# Arch_GPRS.net
KiCad netlist of a schematic drawn in EAGLE
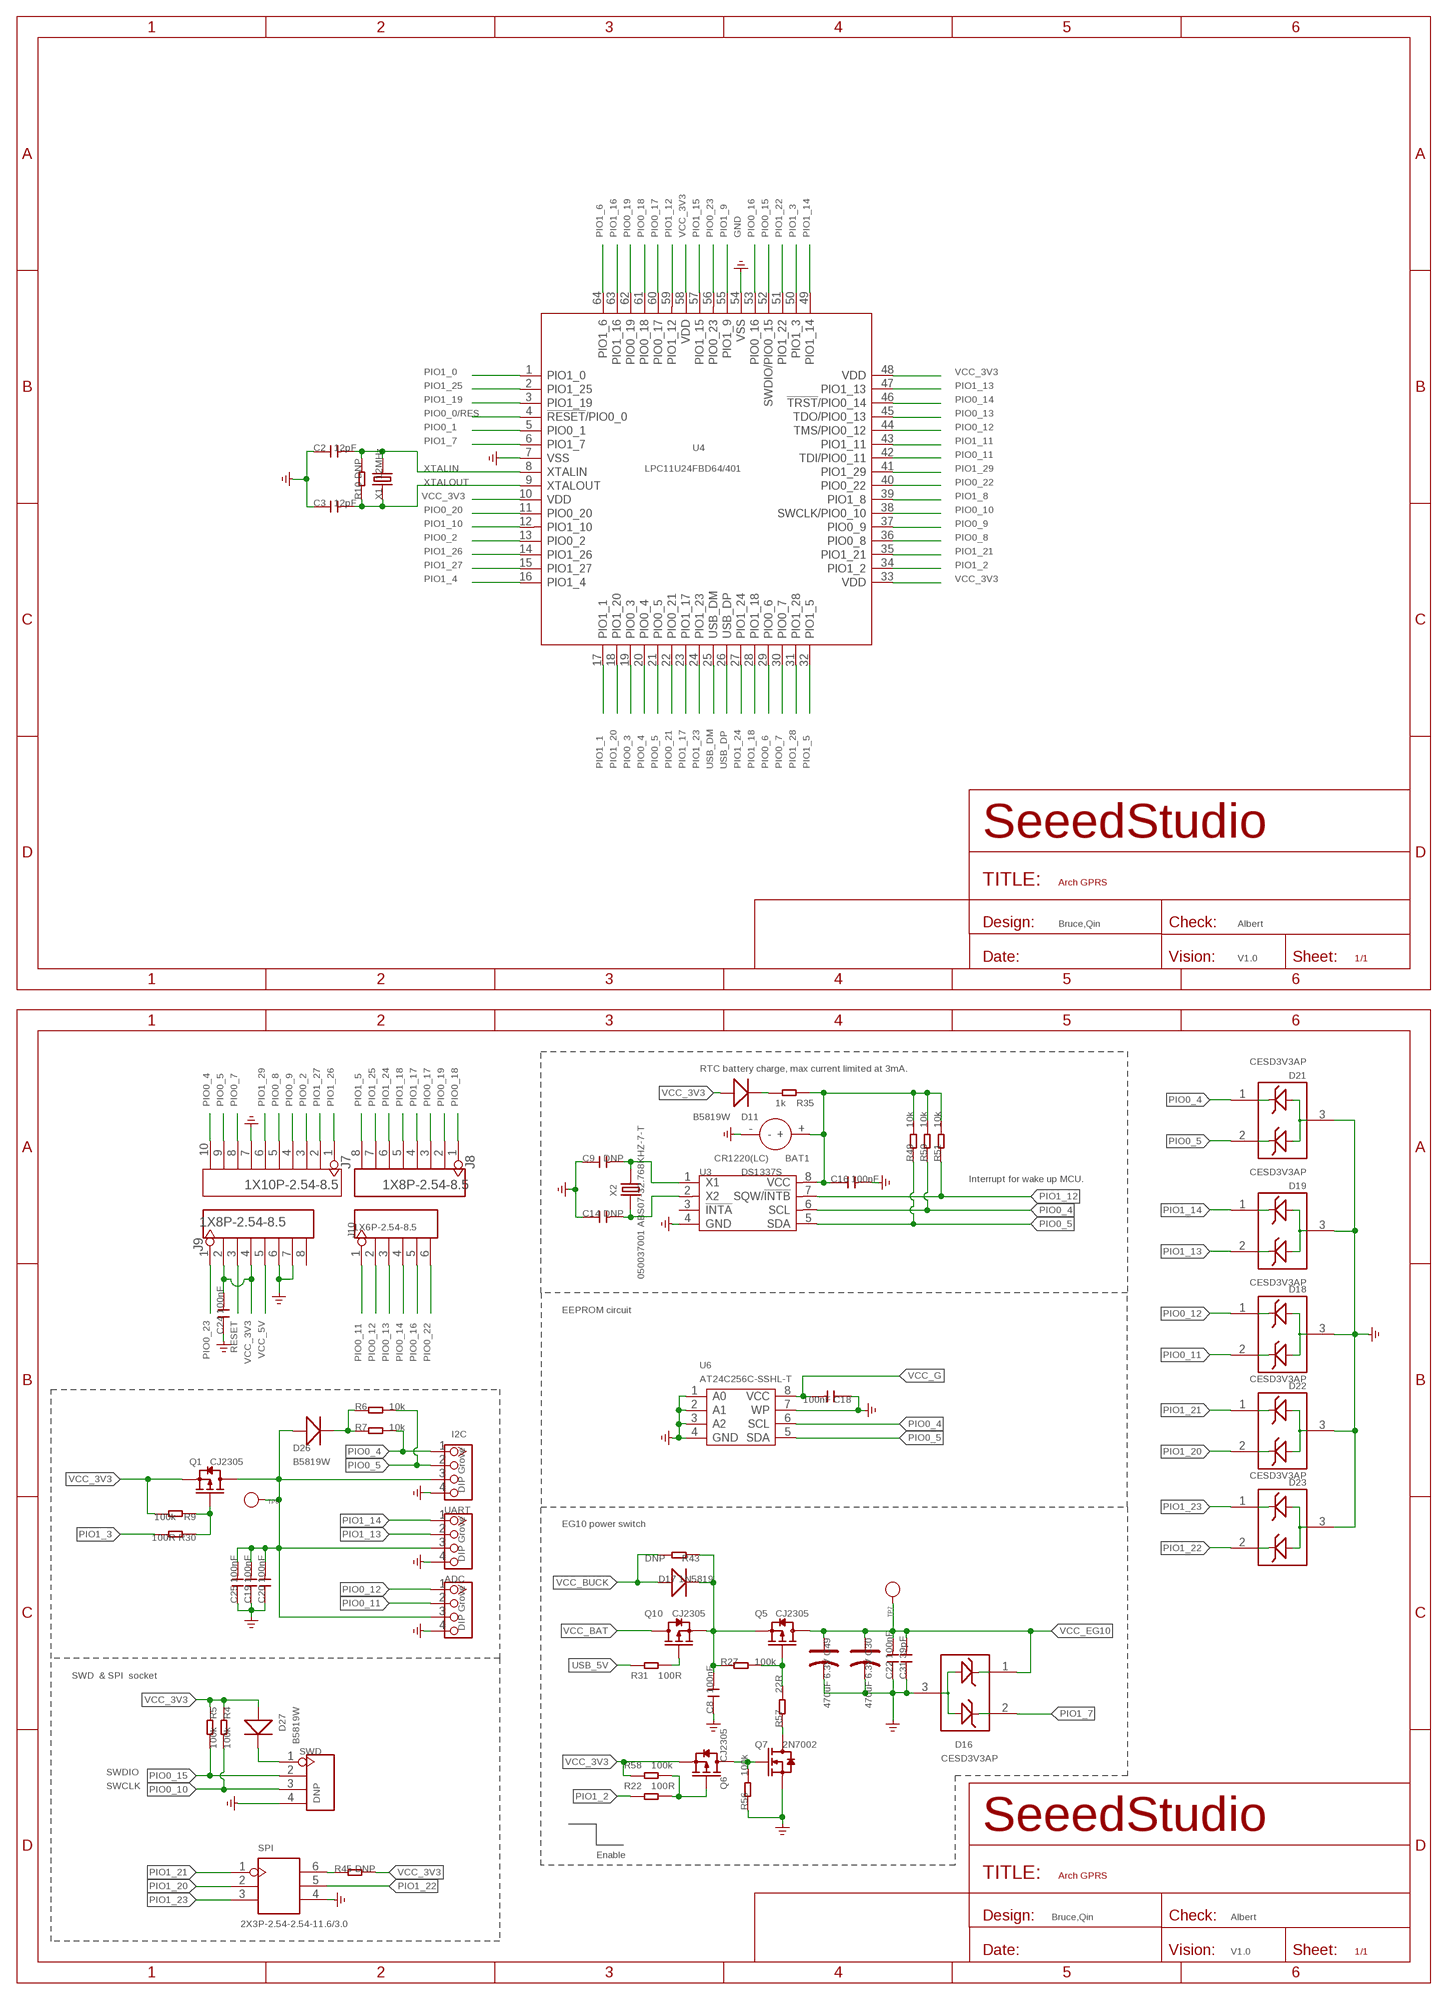
[diagram p0: schematic, sheet 1, part 1 of 2]
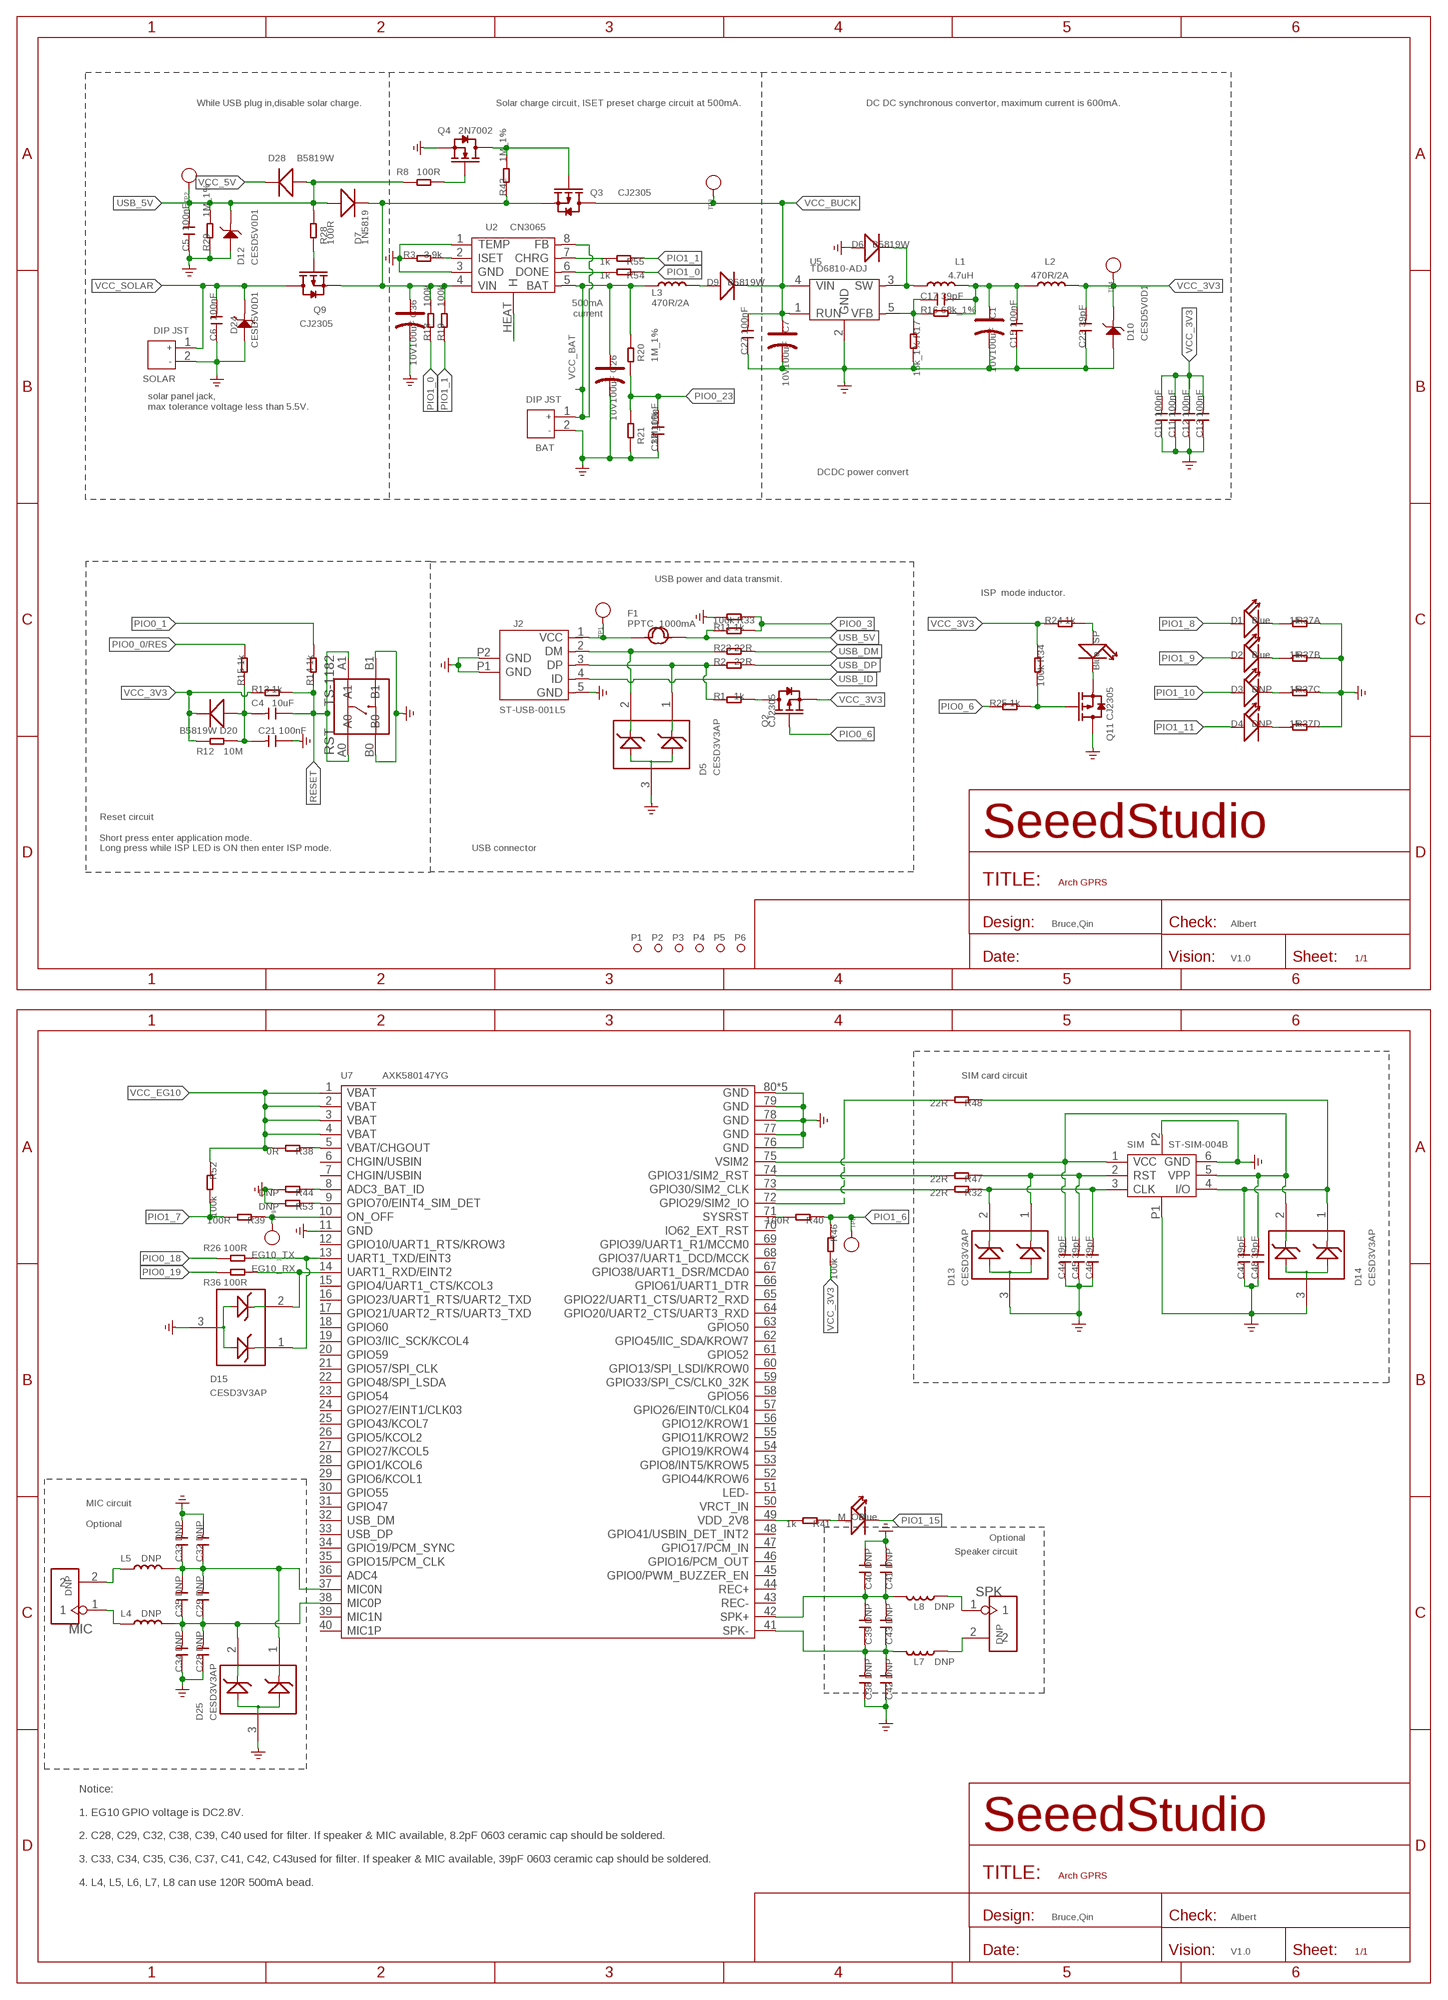
[diagram p1: schematic, sheet 1, part 2 of 2]

(export (version "E")
  (design (tool "Eeschema 10.0.6"))
  (components
    (comp (ref "ADC")
      (value "DIP Grove")
      (footprint "eagle-import:4P-2.0")
      (libsource (lib "eagle-import") (part "TWIG-4P-2.0-2.0"))
    )
    (comp (ref "BAT")
      (value "DIP JST")
      (footprint "eagle-import:JST-2.0")
      (libsource (lib "eagle-import") (part "JACK-JST-2P-PW'2.0'"))
    )
    (comp (ref "BAT1")
      (value "CR1220(LC)")
      (footprint "eagle-import:2P-D12.55X2.22H")
      (libsource (lib "eagle-import") (part "BATTERY-3V"))
    )
    (comp (ref "C1")
      (value "10V100uF")
      (footprint "eagle-import:AVX-B")
      (libsource (lib "eagle-import") (part "CAP-AVX-B"))
    )
    (comp (ref "C2")
      (value "12pF")
      (footprint "eagle-import:C0603")
      (libsource (lib "eagle-import") (part "C-0603"))
    )
    (comp (ref "C3")
      (value "12pF")
      (footprint "eagle-import:C0603")
      (libsource (lib "eagle-import") (part "C-0603"))
    )
    (comp (ref "C4")
      (value "10uF")
      (footprint "eagle-import:C0805")
      (libsource (lib "eagle-import") (part "C-0805"))
    )
    (comp (ref "C5")
      (value "100nF")
      (footprint "eagle-import:C0603")
      (libsource (lib "eagle-import") (part "C-0603"))
    )
    (comp (ref "C6")
      (value "100nF")
      (footprint "eagle-import:C0603")
      (libsource (lib "eagle-import") (part "C-0603"))
    )
    (comp (ref "C7")
      (value "10V100uF")
      (footprint "eagle-import:AVX-B")
      (libsource (lib "eagle-import") (part "CAP-AVX-B"))
    )
    (comp (ref "C8")
      (value "100nF")
      (footprint "eagle-import:C0603")
      (libsource (lib "eagle-import") (part "C-0603"))
    )
    (comp (ref "C9")
      (value "DNP")
      (footprint "eagle-import:C0603")
      (libsource (lib "eagle-import") (part "C-0603"))
    )
    (comp (ref "C10")
      (value "100nF")
      (footprint "eagle-import:C0603")
      (libsource (lib "eagle-import") (part "C-0603"))
    )
    (comp (ref "C11")
      (value "100nF")
      (footprint "eagle-import:C0603")
      (libsource (lib "eagle-import") (part "C-0603"))
    )
    (comp (ref "C12")
      (value "100nF")
      (footprint "eagle-import:C0603")
      (libsource (lib "eagle-import") (part "C-0603"))
    )
    (comp (ref "C13")
      (value "100nF")
      (footprint "eagle-import:C0603")
      (libsource (lib "eagle-import") (part "C-0603"))
    )
    (comp (ref "C14")
      (value "DNP")
      (footprint "eagle-import:C0603")
      (libsource (lib "eagle-import") (part "C-0603"))
    )
    (comp (ref "C15")
      (value "100nF")
      (footprint "eagle-import:C0603")
      (libsource (lib "eagle-import") (part "C-0603"))
    )
    (comp (ref "C16")
      (value "100nF")
      (footprint "eagle-import:C0603")
      (libsource (lib "eagle-import") (part "C-0603"))
    )
    (comp (ref "C17")
      (value "39pF")
      (footprint "eagle-import:C0603")
      (libsource (lib "eagle-import") (part "C-0603"))
    )
    (comp (ref "C18")
      (value "100nF")
      (footprint "eagle-import:C0603")
      (libsource (lib "eagle-import") (part "Discrete (1)_C-0603"))
    )
    (comp (ref "C19")
      (value "100nF")
      (footprint "eagle-import:C0603")
      (libsource (lib "eagle-import") (part "C-0603"))
    )
    (comp (ref "C20")
      (value "100nF")
      (footprint "eagle-import:C0603")
      (libsource (lib "eagle-import") (part "C-0603"))
    )
    (comp (ref "C21")
      (value "100nF")
      (footprint "eagle-import:C0603")
      (libsource (lib "eagle-import") (part "C-0603"))
    )
    (comp (ref "C22")
      (value "100nF")
      (footprint "eagle-import:C0603")
      (libsource (lib "eagle-import") (part "C-0603"))
    )
    (comp (ref "C23")
      (value "39pF")
      (footprint "eagle-import:C0603")
      (libsource (lib "eagle-import") (part "C-0603"))
    )
    (comp (ref "C24")
      (value "100nF")
      (footprint "eagle-import:C0603")
      (libsource (lib "eagle-import") (part "C-0603"))
    )
    (comp (ref "C25")
      (value "100nF")
      (footprint "eagle-import:C0603")
      (libsource (lib "eagle-import") (part "C-0603"))
    )
    (comp (ref "C26")
      (value "10V100uF")
      (footprint "eagle-import:AVX-B")
      (libsource (lib "eagle-import") (part "CAP-AVX-B"))
    )
    (comp (ref "C27")
      (value "100nF")
      (footprint "eagle-import:C0603")
      (libsource (lib "eagle-import") (part "C-0603"))
    )
    (comp (ref "C28")
      (value "DNP")
      (footprint "eagle-import:C0603")
      (libsource (lib "eagle-import") (part "C-0603"))
    )
    (comp (ref "C29")
      (value "DNP")
      (footprint "eagle-import:C0603")
      (libsource (lib "eagle-import") (part "C-0603"))
    )
    (comp (ref "C30")
      (value "470uF 6.3V")
      (footprint "eagle-import:AVX-D")
      (libsource (lib "eagle-import") (part "CAP-AVX-D"))
    )
    (comp (ref "C31")
      (value "39pF")
      (footprint "eagle-import:C0603")
      (libsource (lib "eagle-import") (part "C-0603"))
    )
    (comp (ref "C32")
      (value "DNP")
      (footprint "eagle-import:C0603")
      (libsource (lib "eagle-import") (part "C-0603"))
    )
    (comp (ref "C33")
      (value "DNP")
      (footprint "eagle-import:C0603")
      (libsource (lib "eagle-import") (part "C-0603"))
    )
    (comp (ref "C34")
      (value "DNP")
      (footprint "eagle-import:C0603")
      (libsource (lib "eagle-import") (part "C-0603"))
    )
    (comp (ref "C35")
      (value "DNP")
      (footprint "eagle-import:C0603")
      (libsource (lib "eagle-import") (part "C-0603"))
    )
    (comp (ref "C36")
      (value "10V100uF")
      (footprint "eagle-import:AVX-B")
      (libsource (lib "eagle-import") (part "CAP-AVX-B"))
    )
    (comp (ref "C37")
      (value "100nF")
      (footprint "eagle-import:C0603")
      (libsource (lib "eagle-import") (part "C-0603"))
    )
    (comp (ref "C38")
      (value "DNP")
      (footprint "eagle-import:C0603")
      (libsource (lib "eagle-import") (part "C-0603"))
    )
    (comp (ref "C39")
      (value "DNP")
      (footprint "eagle-import:C0603")
      (libsource (lib "eagle-import") (part "C-0603"))
    )
    (comp (ref "C40")
      (value "DNP")
      (footprint "eagle-import:C0603")
      (libsource (lib "eagle-import") (part "C-0603"))
    )
    (comp (ref "C41")
      (value "DNP")
      (footprint "eagle-import:C0603")
      (libsource (lib "eagle-import") (part "C-0603"))
    )
    (comp (ref "C42")
      (value "DNP")
      (footprint "eagle-import:C0603")
      (libsource (lib "eagle-import") (part "C-0603"))
    )
    (comp (ref "C43")
      (value "DNP")
      (footprint "eagle-import:C0603")
      (libsource (lib "eagle-import") (part "C-0603"))
    )
    (comp (ref "C44")
      (value "39pF")
      (footprint "eagle-import:C0603")
      (libsource (lib "eagle-import") (part "C-0603"))
    )
    (comp (ref "C45")
      (value "39pF")
      (footprint "eagle-import:C0603")
      (libsource (lib "eagle-import") (part "C-0603"))
    )
    (comp (ref "C46")
      (value "39pF")
      (footprint "eagle-import:C0603")
      (libsource (lib "eagle-import") (part "C-0603"))
    )
    (comp (ref "C47")
      (value "39pF")
      (footprint "eagle-import:C0603")
      (libsource (lib "eagle-import") (part "C-0603"))
    )
    (comp (ref "C48")
      (value "39pF")
      (footprint "eagle-import:C0603")
      (libsource (lib "eagle-import") (part "C-0603"))
    )
    (comp (ref "C49")
      (value "470uF 6.3V")
      (footprint "eagle-import:AVX-D")
      (libsource (lib "eagle-import") (part "CAP-AVX-D"))
    )
    (comp (ref "D1")
      (value "Blue")
      (footprint "eagle-import:LED-0603")
      (libsource (lib "eagle-import") (part "LED'0603'"))
    )
    (comp (ref "D2")
      (value "Blue")
      (footprint "eagle-import:LED-0603")
      (libsource (lib "eagle-import") (part "LED'0603'"))
    )
    (comp (ref "D3")
      (value "DNP")
      (footprint "eagle-import:LED-0603")
      (libsource (lib "eagle-import") (part "LED'0603'"))
    )
    (comp (ref "D4")
      (value "DNP")
      (footprint "eagle-import:LED-0603")
      (libsource (lib "eagle-import") (part "LED'0603'"))
    )
    (comp (ref "D5")
      (value "CESD3V3AP")
      (footprint "eagle-import:SOT23")
      (libsource (lib "eagle-import") (part "D-ESD-3P"))
    )
    (comp (ref "D6")
      (value "B5819W")
      (footprint "eagle-import:SOD123")
      (libsource (lib "eagle-import") (part "D'1206'"))
    )
    (comp (ref "D7")
      (value "1N5819")
      (footprint "eagle-import:SMA")
      (libsource (lib "eagle-import") (part "D'B130L-13-F'"))
    )
    (comp (ref "D9")
      (value "B5819W")
      (footprint "eagle-import:SOD123")
      (libsource (lib "eagle-import") (part "D'1206'"))
    )
    (comp (ref "D10")
      (value "CESD5V0D1")
      (footprint "eagle-import:SOD123-2.7X1.6")
      (libsource (lib "eagle-import") (part "D-ESD-2P'CESD5V0D1'"))
    )
    (comp (ref "D11")
      (value "B5819W")
      (footprint "eagle-import:SOD123")
      (libsource (lib "eagle-import") (part "D'1206'"))
    )
    (comp (ref "D12")
      (value "CESD5V0D1")
      (footprint "eagle-import:SOD123-2.7X1.6")
      (libsource (lib "eagle-import") (part "D-ESD-2P'CESD5V0D1'"))
    )
    (comp (ref "D13")
      (value "CESD3V3AP")
      (footprint "eagle-import:SOT23")
      (libsource (lib "eagle-import") (part "D-ESD-3P"))
    )
    (comp (ref "D14")
      (value "CESD3V3AP")
      (footprint "eagle-import:SOT23")
      (libsource (lib "eagle-import") (part "D-ESD-3P"))
    )
    (comp (ref "D15")
      (value "CESD3V3AP")
      (footprint "eagle-import:SOT23")
      (libsource (lib "eagle-import") (part "D-ESD-3P"))
    )
    (comp (ref "D16")
      (value "CESD3V3AP")
      (footprint "eagle-import:SOT23")
      (libsource (lib "eagle-import") (part "D-ESD-3P"))
    )
    (comp (ref "D17")
      (value "1N5819")
      (footprint "eagle-import:SMA")
      (libsource (lib "eagle-import") (part "D'B130L-13-F'"))
    )
    (comp (ref "D18")
      (value "CESD3V3AP")
      (footprint "eagle-import:SOT23")
      (libsource (lib "eagle-import") (part "D-ESD-3P"))
    )
    (comp (ref "D19")
      (value "CESD3V3AP")
      (footprint "eagle-import:SOT23")
      (libsource (lib "eagle-import") (part "D-ESD-3P"))
    )
    (comp (ref "D20")
      (value "B5819W")
      (footprint "eagle-import:SOD123")
      (libsource (lib "eagle-import") (part "D'1206'"))
    )
    (comp (ref "D21")
      (value "CESD3V3AP")
      (footprint "eagle-import:SOT23")
      (libsource (lib "eagle-import") (part "D-ESD-3P"))
    )
    (comp (ref "D22")
      (value "CESD3V3AP")
      (footprint "eagle-import:SOT23")
      (libsource (lib "eagle-import") (part "D-ESD-3P"))
    )
    (comp (ref "D23")
      (value "CESD3V3AP")
      (footprint "eagle-import:SOT23")
      (libsource (lib "eagle-import") (part "D-ESD-3P"))
    )
    (comp (ref "D24")
      (value "CESD5V0D1")
      (footprint "eagle-import:SOD123-2.7X1.6")
      (libsource (lib "eagle-import") (part "D-ESD-2P'CESD5V0D1'"))
    )
    (comp (ref "D25")
      (value "CESD3V3AP")
      (footprint "eagle-import:SOT23")
      (libsource (lib "eagle-import") (part "D-ESD-3P"))
    )
    (comp (ref "D26")
      (value "B5819W")
      (footprint "eagle-import:SOD123")
      (libsource (lib "eagle-import") (part "D'1206'"))
    )
    (comp (ref "D27")
      (value "B5819W")
      (footprint "eagle-import:SOD123")
      (libsource (lib "eagle-import") (part "D'1206'"))
    )
    (comp (ref "D28")
      (value "B5819W")
      (footprint "eagle-import:SOD123")
      (libsource (lib "eagle-import") (part "D'1206'"))
    )
    (comp (ref "F1")
      (value "PPTC_1000mA")
      (footprint "eagle-import:F1206")
      (libsource (lib "eagle-import") (part "FUSE'1206'"))
    )
    (comp (ref "I2C")
      (value "DIP Grove")
      (footprint "eagle-import:4P-2.0")
      (libsource (lib "eagle-import") (part "TWIG-4P-2.0-2.0"))
    )
    (comp (ref "ISP")
      (value "Blue")
      (footprint "eagle-import:LED-0603")
      (libsource (lib "eagle-import") (part "LED'0603'"))
    )
    (comp (ref "J2")
      (value "ST-USB-001L5")
      (footprint "eagle-import:MICRO-5P-180D")
      (libsource (lib "eagle-import") (part "USB-MICRO-5P'ST-USB-001L5'"))
    )
    (comp (ref "J7")
      (value "1X10P-2.54-8.5")
      (footprint "eagle-import:10P-2.54")
      (libsource (lib "eagle-import") (part "HEADER-10P-2.54"))
    )
    (comp (ref "J8")
      (value "1X8P-2.54-8.5")
      (footprint "eagle-import:8P-2.54")
      (libsource (lib "eagle-import") (part "HEADER-8P-2.54"))
    )
    (comp (ref "J9")
      (value "1X8P-2.54-8.5")
      (footprint "eagle-import:8P-2.54")
      (libsource (lib "eagle-import") (part "HEADER-8P-2.54"))
    )
    (comp (ref "J10")
      (value "1X6P-2.54-8.5")
      (footprint "eagle-import:6P-2.54-65_35MIL")
      (libsource (lib "eagle-import") (part "HEADER-6P-65/35MIL"))
    )
    (comp (ref "L1")
      (value "4.7uH")
      (footprint "eagle-import:L0420")
      (libsource (lib "eagle-import") (part "LSPD3D16-4R7M"))
    )
    (comp (ref "L2")
      (value "470R/2A")
      (footprint "eagle-import:L0805")
      (libsource (lib "eagle-import") (part "L'0805'"))
    )
    (comp (ref "L3")
      (value "470R/2A")
      (footprint "eagle-import:L0805")
      (libsource (lib "eagle-import") (part "L'0805'"))
    )
    (comp (ref "L4")
      (value "DNP")
      (footprint "eagle-import:L0603")
      (libsource (lib "eagle-import") (part "L'0603'"))
    )
    (comp (ref "L5")
      (value "DNP")
      (footprint "eagle-import:L0603")
      (libsource (lib "eagle-import") (part "L'0603'"))
    )
    (comp (ref "L7")
      (value "DNP")
      (footprint "eagle-import:L0603")
      (libsource (lib "eagle-import") (part "L'0603'"))
    )
    (comp (ref "L8")
      (value "DNP")
      (footprint "eagle-import:L0603")
      (libsource (lib "eagle-import") (part "L'0603'"))
    )
    (comp (ref "MIC")
      (value "DNP")
      (footprint "eagle-import:2P-2.0")
      (libsource (lib "eagle-import") (part "HEADER-2P-2.0"))
    )
    (comp (ref "M_ON")
      (value "Blue")
      (footprint "eagle-import:LED-0603")
      (libsource (lib "eagle-import") (part "LED'0603'"))
    )
    (comp (ref "P1")
      (value "PAD-MARK")
      (footprint "eagle-import:ROUND-MARK-1.0")
      (fields (field (name "PARTNO") "DNP"))
      (libsource (lib "eagle-import") (part "PAD-MARK"))
    )
    (comp (ref "P2")
      (value "PAD-MARK")
      (footprint "eagle-import:ROUND-MARK-1.0")
      (fields (field (name "PARTNO") "DNP"))
      (libsource (lib "eagle-import") (part "PAD-MARK"))
    )
    (comp (ref "P3")
      (value "PAD-MARK")
      (footprint "eagle-import:ROUND-MARK-1.0")
      (fields (field (name "PARTNO") "DNP"))
      (libsource (lib "eagle-import") (part "PAD-MARK"))
    )
    (comp (ref "P4")
      (value "PAD-MARK")
      (footprint "eagle-import:ROUND-MARK-1.0")
      (fields (field (name "PARTNO") "DNP"))
      (libsource (lib "eagle-import") (part "PAD-MARK"))
    )
    (comp (ref "P5")
      (value "PAD-MARK")
      (footprint "eagle-import:ROUND-MARK-1.0")
      (fields (field (name "PARTNO") "DNP"))
      (libsource (lib "eagle-import") (part "PAD-MARK"))
    )
    (comp (ref "P6")
      (value "PAD-MARK")
      (footprint "eagle-import:ROUND-MARK-1.0")
      (fields (field (name "PARTNO") "DNP"))
      (libsource (lib "eagle-import") (part "PAD-MARK"))
    )
    (comp (ref "Q1")
      (value "CJ2305")
      (footprint "eagle-import:SOT23")
      (libsource (lib "eagle-import") (part "MOSFET-P'SI2323CDS/SI2305DS{lt}BR{gt}'"))
    )
    (comp (ref "Q2")
      (value "CJ2305")
      (footprint "eagle-import:SOT23")
      (libsource (lib "eagle-import") (part "MOSFET-P'SI2323CDS/SI2305DS{lt}BR{gt}'"))
    )
    (comp (ref "Q3")
      (value "CJ2305")
      (footprint "eagle-import:SOT23")
      (libsource (lib "eagle-import") (part "MOSFET-P'SI2323CDS/SI2305DS{lt}BR{gt}'"))
    )
    (comp (ref "Q4")
      (value "2N7002")
      (footprint "eagle-import:SOT23")
      (libsource (lib "eagle-import") (part "MOSFET-N'SOT23'"))
    )
    (comp (ref "Q5")
      (value "CJ2305")
      (footprint "eagle-import:SOT23")
      (libsource (lib "eagle-import") (part "MOSFET-P'SI2323CDS/SI2305DS{lt}BR{gt}'"))
    )
    (comp (ref "Q6")
      (value "CJ2305")
      (footprint "eagle-import:SOT23")
      (libsource (lib "eagle-import") (part "MOSFET-P'SI2323CDS/SI2305DS{lt}BR{gt}'"))
    )
    (comp (ref "Q7")
      (value "2N7002")
      (footprint "eagle-import:SOT23")
      (libsource (lib "eagle-import") (part "MOSFET-N'SOT23'"))
    )
    (comp (ref "Q9")
      (value "CJ2305")
      (footprint "eagle-import:SOT23")
      (libsource (lib "eagle-import") (part "MOSFET-P'SI2323CDS/SI2305DS{lt}BR{gt}'"))
    )
    (comp (ref "Q10")
      (value "CJ2305")
      (footprint "eagle-import:SOT23")
      (libsource (lib "eagle-import") (part "MOSFET-P'SI2323CDS/SI2305DS{lt}BR{gt}'"))
    )
    (comp (ref "Q11")
      (value "CJ2305")
      (footprint "eagle-import:SOT23")
      (libsource (lib "eagle-import") (part "MOSFET-P'SI2323CDS/SI2305DS{lt}BR{gt}'"))
    )
    (comp (ref "R1")
      (value "1k")
      (footprint "eagle-import:R0603")
      (libsource (lib "eagle-import") (part "R-0603"))
    )
    (comp (ref "R2")
      (value "22R")
      (footprint "eagle-import:R0603")
      (libsource (lib "eagle-import") (part "R-0603"))
    )
    (comp (ref "R3")
      (value "3.9k")
      (footprint "eagle-import:R0603")
      (libsource (lib "eagle-import") (part "R-0603"))
    )
    (comp (ref "R4")
      (value "100k")
      (footprint "eagle-import:R0603")
      (libsource (lib "eagle-import") (part "R-0603"))
    )
    (comp (ref "R5")
      (value "100k")
      (footprint "eagle-import:R0603")
      (libsource (lib "eagle-import") (part "R-0603"))
    )
    (comp (ref "R6")
      (value "10k")
      (footprint "eagle-import:R0603")
      (libsource (lib "eagle-import") (part "R-0603"))
    )
    (comp (ref "R7")
      (value "10k")
      (footprint "eagle-import:R0603")
      (libsource (lib "eagle-import") (part "R-0603"))
    )
    (comp (ref "R8")
      (value "100R")
      (footprint "eagle-import:R0603")
      (libsource (lib "eagle-import") (part "R-0603"))
    )
    (comp (ref "R9")
      (value "100k")
      (footprint "eagle-import:R0603")
      (libsource (lib "eagle-import") (part "R-0603"))
    )
    (comp (ref "R10")
      (value "DNP")
      (footprint "eagle-import:R0603")
      (libsource (lib "eagle-import") (part "R-0603"))
    )
    (comp (ref "R11")
      (value "1k")
      (footprint "eagle-import:R0603")
      (libsource (lib "eagle-import") (part "R-0603"))
    )
    (comp (ref "R12")
      (value "10M")
      (footprint "eagle-import:R0603")
      (libsource (lib "eagle-import") (part "R-0603"))
    )
    (comp (ref "R13")
      (value "1k")
      (footprint "eagle-import:R0603")
      (libsource (lib "eagle-import") (part "R-0603"))
    )
    (comp (ref "R14")
      (value "1k")
      (footprint "eagle-import:R0603")
      (libsource (lib "eagle-import") (part "R-0603"))
    )
    (comp (ref "R15")
      (value "1k")
      (footprint "eagle-import:R0603")
      (libsource (lib "eagle-import") (part "R-0603"))
    )
    (comp (ref "R16")
      (value "68k_1%")
      (footprint "eagle-import:R0603")
      (libsource (lib "eagle-import") (part "R-0603"))
    )
    (comp (ref "R17")
      (value "15k_1%")
      (footprint "eagle-import:R0603")
      (libsource (lib "eagle-import") (part "R-0603"))
    )
    (comp (ref "R18")
      (value "100k")
      (footprint "eagle-import:R0603")
      (libsource (lib "eagle-import") (part "R-0603"))
    )
    (comp (ref "R19")
      (value "100k")
      (footprint "eagle-import:R0603")
      (libsource (lib "eagle-import") (part "R-0603"))
    )
    (comp (ref "R20")
      (value "1M_1%")
      (footprint "eagle-import:R0603")
      (libsource (lib "eagle-import") (part "R-0603"))
    )
    (comp (ref "R21")
      (value "1M_1%")
      (footprint "eagle-import:R0603")
      (libsource (lib "eagle-import") (part "R-0603"))
    )
    (comp (ref "R22")
      (value "100R")
      (footprint "eagle-import:R0603")
      (libsource (lib "eagle-import") (part "R-0603"))
    )
    (comp (ref "R23")
      (value "22R")
      (footprint "eagle-import:R0603")
      (libsource (lib "eagle-import") (part "R-0603"))
    )
    (comp (ref "R24")
      (value "1k")
      (footprint "eagle-import:R0603")
      (libsource (lib "eagle-import") (part "R-0603"))
    )
    (comp (ref "R25")
      (value "1k")
      (footprint "eagle-import:R0603")
      (libsource (lib "eagle-import") (part "R-0603"))
    )
    (comp (ref "R26")
      (value "100R")
      (footprint "eagle-import:R0603")
      (libsource (lib "eagle-import") (part "R-0603"))
    )
    (comp (ref "R27")
      (value "100k")
      (footprint "eagle-import:R0603")
      (libsource (lib "eagle-import") (part "R-0603"))
    )
    (comp (ref "R28")
      (value "100R")
      (footprint "eagle-import:R0603")
      (libsource (lib "eagle-import") (part "R-0603"))
    )
    (comp (ref "R29")
      (value "1M_1%")
      (footprint "eagle-import:R0603")
      (libsource (lib "eagle-import") (part "R-0603"))
    )
    (comp (ref "R30")
      (value "100R")
      (footprint "eagle-import:R0603")
      (libsource (lib "eagle-import") (part "R-0603"))
    )
    (comp (ref "R31")
      (value "100R")
      (footprint "eagle-import:R0603")
      (libsource (lib "eagle-import") (part "R-0603"))
    )
    (comp (ref "R32")
      (value "22R")
      (footprint "eagle-import:R0603")
      (libsource (lib "eagle-import") (part "R-0603"))
    )
    (comp (ref "R33")
      (value "100k")
      (footprint "eagle-import:R0603")
      (libsource (lib "eagle-import") (part "R-0603"))
    )
    (comp (ref "R34")
      (value "100k")
      (footprint "eagle-import:R0603")
      (libsource (lib "eagle-import") (part "R-0603"))
    )
    (comp (ref "R35")
      (value "1k")
      (footprint "eagle-import:R0603")
      (libsource (lib "eagle-import") (part "R-0603"))
    )
    (comp (ref "R36")
      (value "100R")
      (footprint "eagle-import:R0603")
      (libsource (lib "eagle-import") (part "R-0603"))
    )
    (comp (ref "R37")
      (value "1k")
      (footprint "eagle-import:1206-8-3.3X2.4")
      (libsource (lib "eagle-import") (part "R-4R-1206"))
    )
    (comp (ref "R38")
      (value "0R")
      (footprint "eagle-import:R0603")
      (libsource (lib "eagle-import") (part "R-0603"))
    )
    (comp (ref "R39")
      (value "100R")
      (footprint "eagle-import:R0603")
      (libsource (lib "eagle-import") (part "R-0603"))
    )
    (comp (ref "R40")
      (value "100R")
      (footprint "eagle-import:R0603")
      (libsource (lib "eagle-import") (part "R-0603"))
    )
    (comp (ref "R41")
      (value "1k")
      (footprint "eagle-import:R0603")
      (libsource (lib "eagle-import") (part "R-0603"))
    )
    (comp (ref "R42")
      (value "1M_1%")
      (footprint "eagle-import:R0603")
      (libsource (lib "eagle-import") (part "R-0603"))
    )
    (comp (ref "R43")
      (value "DNP")
      (footprint "eagle-import:R0603")
      (libsource (lib "eagle-import") (part "R-0603"))
    )
    (comp (ref "R44")
      (value "DNP")
      (footprint "eagle-import:R0603")
      (libsource (lib "eagle-import") (part "R-0603"))
    )
    (comp (ref "R45")
      (value "DNP")
      (footprint "eagle-import:R0603")
      (libsource (lib "eagle-import") (part "R-0603"))
    )
    (comp (ref "R46")
      (value "100k")
      (footprint "eagle-import:R0603")
      (libsource (lib "eagle-import") (part "R-0603"))
    )
    (comp (ref "R47")
      (value "22R")
      (footprint "eagle-import:R0603")
      (libsource (lib "eagle-import") (part "R-0603"))
    )
    (comp (ref "R48")
      (value "22R")
      (footprint "eagle-import:R0603")
      (libsource (lib "eagle-import") (part "R-0603"))
    )
    (comp (ref "R49")
      (value "10k")
      (footprint "eagle-import:R0603")
      (libsource (lib "eagle-import") (part "R-0603"))
    )
    (comp (ref "R50")
      (value "10k")
      (footprint "eagle-import:R0603")
      (libsource (lib "eagle-import") (part "R-0603"))
    )
    (comp (ref "R51")
      (value "10k")
      (footprint "eagle-import:R0603")
      (libsource (lib "eagle-import") (part "R-0603"))
    )
    (comp (ref "R52")
      (value "100k")
      (footprint "eagle-import:R0603")
      (libsource (lib "eagle-import") (part "R-0603"))
    )
    (comp (ref "R53")
      (value "DNP")
      (footprint "eagle-import:R0603")
      (libsource (lib "eagle-import") (part "R-0603"))
    )
    (comp (ref "R54")
      (value "1k")
      (footprint "eagle-import:R0603")
      (libsource (lib "eagle-import") (part "R-0603"))
    )
    (comp (ref "R55")
      (value "1k")
      (footprint "eagle-import:R0603")
      (libsource (lib "eagle-import") (part "R-0603"))
    )
    (comp (ref "R56")
      (value "100k")
      (footprint "eagle-import:R0603")
      (libsource (lib "eagle-import") (part "R-0603"))
    )
    (comp (ref "R57")
      (value "22R")
      (footprint "eagle-import:R0603")
      (libsource (lib "eagle-import") (part "R-0603"))
    )
    (comp (ref "R58")
      (value "100k")
      (footprint "eagle-import:R0603")
      (libsource (lib "eagle-import") (part "R-0603"))
    )
    (comp (ref "RST")
      (value "TS-1182")
      (footprint "eagle-import:4P-SMD-3.4X3.4X1.3H")
      (libsource (lib "eagle-import") (part "BUTTON-4P-3.3X3.3"))
    )
    (comp (ref "SIM")
      (value "ST-SIM-004B")
      (footprint "eagle-import:6P-1.8")
      (libsource (lib "eagle-import") (part "SIM-CARD'ST-SIM-004B'"))
    )
    (comp (ref "SOLAR")
      (value "DIP JST")
      (footprint "eagle-import:JST-2.0")
      (libsource (lib "eagle-import") (part "JACK-JST-2P-PW'2.0'"))
    )
    (comp (ref "SPI")
      (value "2X3P-2.54-2.54-11.6/3.0")
      (footprint "eagle-import:2X3P-2.54")
      (libsource (lib "eagle-import") (part "HEADER-2X3P-2.54"))
    )
    (comp (ref "SPK")
      (value "DNP")
      (footprint "eagle-import:2P-2.0")
      (libsource (lib "eagle-import") (part "HEADER-2P-2.0"))
    )
    (comp (ref "SWD")
      (value "DNP")
      (footprint "eagle-import:4P-65_35MIL")
      (libsource (lib "eagle-import") (part "HEADER-4P-65/35MIL"))
    )
    (comp (ref "TP1")
      (value "PAD-TEST-POINT'4545'")
      (footprint "eagle-import:TP_4545")
      (fields (field (name "PARTNO") "DNP"))
      (libsource (lib "eagle-import") (part "PAD-TEST-POINT'4545'"))
    )
    (comp (ref "TP2")
      (value "PAD-TEST-POINT'4545'")
      (footprint "eagle-import:TP_4545")
      (fields (field (name "PARTNO") "DNP"))
      (libsource (lib "eagle-import") (part "PAD-TEST-POINT'4545'"))
    )
    (comp (ref "TP3")
      (value "PAD-TEST-POINT'4545'")
      (footprint "eagle-import:TP_4545")
      (fields (field (name "PARTNO") "DNP"))
      (libsource (lib "eagle-import") (part "PAD-TEST-POINT'4545'"))
    )
    (comp (ref "TP4")
      (value "PAD-TEST-POINT'4545'")
      (footprint "eagle-import:TP_4545")
      (fields (field (name "PARTNO") "DNP"))
      (libsource (lib "eagle-import") (part "PAD-TEST-POINT'4545'"))
    )
    (comp (ref "TP6")
      (value "PAD-TEST-POINT'4545'")
      (footprint "eagle-import:TP_4545")
      (fields (field (name "PARTNO") "DNP"))
      (libsource (lib "eagle-import") (part "PAD-TEST-POINT'4545'"))
    )
    (comp (ref "TP7")
      (value "PAD-TEST-POINT'4545'")
      (footprint "eagle-import:TP_4545")
      (fields (field (name "PARTNO") "DNP"))
      (libsource (lib "eagle-import") (part "PAD-TEST-POINT'4545'"))
    )
    (comp (ref "TP8")
      (value "PAD-TEST-POINT'4545'")
      (footprint "eagle-import:TP_4545")
      (fields (field (name "PARTNO") "DNP"))
      (libsource (lib "eagle-import") (part "PAD-TEST-POINT'4545'"))
    )
    (comp (ref "TP9")
      (value "PAD-TEST-POINT'4545'")
      (footprint "eagle-import:TP_4545")
      (fields (field (name "PARTNO") "DNP"))
      (libsource (lib "eagle-import") (part "PAD-TEST-POINT'4545'"))
    )
    (comp (ref "U2")
      (value "CN3065")
      (footprint "eagle-import:DFN8")
      (libsource (lib "eagle-import") (part "CN3065-DFN8"))
    )
    (comp (ref "U3")
      (value "DS1337S")
      (footprint "eagle-import:SOP8")
      (libsource (lib "eagle-import") (part "DS1337S"))
    )
    (comp (ref "U4")
      (value "LPC11U24FBD64/401")
      (footprint "eagle-import:LQFP64")
      (libsource (lib "eagle-import") (part "LPC11U2X'LPC11U24FBD64/401'"))
    )
    (comp (ref "U5")
      (value "TD6810-ADJ")
      (footprint "eagle-import:SOT23-5")
      (libsource (lib "eagle-import") (part "TD6810'TSOT23-5'"))
    )
    (comp (ref "U6")
      (value "AT24C256C-SSHL-T")
      (footprint "eagle-import:SOIC8-6.0")
      (libsource (lib "eagle-import") (part "AT24C256C'"))
    )
    (comp (ref "U7")
      (value "AXK580147YG")
      (footprint "eagle-import:80P-0.5-3H")
      (libsource (lib "eagle-import") (part "GPRS-MOUDLE-SOCKET'AXK580147YG'"))
    )
    (comp (ref "UART")
      (value "DIP Grove")
      (footprint "eagle-import:4P-2.0")
      (libsource (lib "eagle-import") (part "TWIG-4P-2.0-2.0"))
    )
    (comp (ref "X1")
      (value "12MHz")
      (footprint "eagle-import:2P-SMD-5X3.2")
      (libsource (lib "eagle-import") (part "CRYSTAL'5032'"))
    )
    (comp (ref "X2")
      (value "050037001 ABS07-32.768KHZ-7-T")
      (footprint "eagle-import:2P-SMD-3.2X1.5")
      (libsource (lib "eagle-import") (part "CRYSTAL-3215"))
    )
  )
  (nets
    (net (code "1") (name "/EG10_RX") (class "Default")
      (node (ref "D15") (pin "2") (pinfunction "2_2") (pintype "bidirectional"))
      (node (ref "R36") (pin "1") (pinfunction "1_1") (pintype "passive"))
      (node (ref "U7") (pin "14") (pinfunction "UART1_RXD/EINT2_14") (pintype "bidirectional"))
    )
    (net (code "2") (name "/EG10_TX") (class "Default")
      (node (ref "D15") (pin "1") (pinfunction "1_1") (pintype "bidirectional"))
      (node (ref "R26") (pin "1") (pinfunction "1_1") (pintype "passive"))
      (node (ref "U7") (pin "13") (pinfunction "UART1_TXD/EINT3_13") (pintype "bidirectional"))
    )
    (net (code "3") (name "/PIO0_2") (class "Default")
      (node (ref "J7") (pin "3") (pinfunction "3_3") (pintype "bidirectional"))
      (node (ref "U4") (pin "13") (pinfunction "PIO0_2_13") (pintype "bidirectional"))
    )
    (net (code "4") (name "/PIO0_7") (class "Default")
      (node (ref "J7") (pin "8") (pinfunction "8_8") (pintype "bidirectional"))
      (node (ref "U4") (pin "30") (pinfunction "PIO0_7_30") (pintype "bidirectional"))
    )
    (net (code "5") (name "/PIO0_8") (class "Default")
      (node (ref "J7") (pin "5") (pinfunction "5_5") (pintype "bidirectional"))
      (node (ref "U4") (pin "36") (pinfunction "PIO0_8_36") (pintype "bidirectional"))
    )
    (net (code "6") (name "/PIO0_9") (class "Default")
      (node (ref "J7") (pin "4") (pinfunction "4_4") (pintype "bidirectional"))
      (node (ref "U4") (pin "37") (pinfunction "PIO0_9_37") (pintype "bidirectional"))
    )
    (net (code "7") (name "/PIO0_13") (class "Default")
      (node (ref "J10") (pin "3") (pinfunction "3_3") (pintype "bidirectional"))
      (node (ref "U4") (pin "45") (pinfunction "TDO/PIO0_13_45") (pintype "bidirectional"))
    )
    (net (code "8") (name "/PIO0_14") (class "Default")
      (node (ref "J10") (pin "4") (pinfunction "4_4") (pintype "bidirectional"))
      (node (ref "U4") (pin "46") (pinfunction "~{TRST}/PIO0_14_46") (pintype "bidirectional"))
    )
    (net (code "9") (name "/PIO0_16") (class "Default")
      (node (ref "J10") (pin "5") (pinfunction "5_5") (pintype "bidirectional"))
      (node (ref "U4") (pin "53") (pinfunction "PIO0_16_53") (pintype "bidirectional"))
    )
    (net (code "10") (name "/PIO0_17") (class "Default")
      (node (ref "J8") (pin "3") (pinfunction "3_3") (pintype "bidirectional"))
      (node (ref "U4") (pin "60") (pinfunction "PIO0_17_60") (pintype "bidirectional"))
    )
    (net (code "11") (name "/PIO0_20") (class "Default")
      (node (ref "U4") (pin "11") (pinfunction "PIO0_20_11") (pintype "bidirectional"))
    )
    (net (code "12") (name "/PIO0_21") (class "Default")
      (node (ref "U4") (pin "22") (pinfunction "PIO0_21_22") (pintype "bidirectional"))
    )
    (net (code "13") (name "/PIO0_22") (class "Default")
      (node (ref "J10") (pin "6") (pinfunction "6_6") (pintype "bidirectional"))
      (node (ref "U4") (pin "40") (pinfunction "PIO0_22_40") (pintype "bidirectional"))
    )
    (net (code "14") (name "/PIO1_4") (class "Default")
      (node (ref "U4") (pin "16") (pinfunction "PIO1_4_16") (pintype "bidirectional"))
    )
    (net (code "15") (name "/PIO1_5") (class "Default")
      (node (ref "J8") (pin "8") (pinfunction "8_8") (pintype "bidirectional"))
      (node (ref "U4") (pin "32") (pinfunction "PIO1_5_32") (pintype "bidirectional"))
    )
    (net (code "16") (name "/PIO1_16") (class "Default")
      (node (ref "U4") (pin "63") (pinfunction "PIO1_16_63") (pintype "bidirectional"))
    )
    (net (code "17") (name "/PIO1_17") (class "Default")
      (node (ref "J8") (pin "4") (pinfunction "4_4") (pintype "bidirectional"))
      (node (ref "U4") (pin "23") (pinfunction "PIO1_17_23") (pintype "bidirectional"))
    )
    (net (code "18") (name "/PIO1_18") (class "Default")
      (node (ref "J8") (pin "5") (pinfunction "5_5") (pintype "bidirectional"))
      (node (ref "U4") (pin "28") (pinfunction "PIO1_18_28") (pintype "bidirectional"))
    )
    (net (code "19") (name "/PIO1_19") (class "Default")
      (node (ref "U4") (pin "3") (pinfunction "PIO1_19_3") (pintype "bidirectional"))
    )
    (net (code "20") (name "/PIO1_24") (class "Default")
      (node (ref "J8") (pin "6") (pinfunction "6_6") (pintype "bidirectional"))
      (node (ref "U4") (pin "27") (pinfunction "PIO1_24_27") (pintype "bidirectional"))
    )
    (net (code "21") (name "/PIO1_25") (class "Default")
      (node (ref "J8") (pin "7") (pinfunction "7_7") (pintype "bidirectional"))
      (node (ref "U4") (pin "2") (pinfunction "PIO1_25_2") (pintype "bidirectional"))
    )
    (net (code "22") (name "/PIO1_26") (class "Default")
      (node (ref "J7") (pin "1") (pinfunction "1_1") (pintype "bidirectional"))
      (node (ref "U4") (pin "14") (pinfunction "PIO1_26_14") (pintype "bidirectional"))
    )
    (net (code "23") (name "/PIO1_27") (class "Default")
      (node (ref "J7") (pin "2") (pinfunction "2_2") (pintype "bidirectional"))
      (node (ref "U4") (pin "15") (pinfunction "PIO1_27_15") (pintype "bidirectional"))
    )
    (net (code "24") (name "/PIO1_28") (class "Default")
      (node (ref "U4") (pin "31") (pinfunction "PIO1_28_31") (pintype "bidirectional"))
    )
    (net (code "25") (name "/PIO1_29") (class "Default")
      (node (ref "J7") (pin "6") (pinfunction "6_6") (pintype "bidirectional"))
      (node (ref "U4") (pin "41") (pinfunction "PIO1_29_41") (pintype "bidirectional"))
    )
    (net (code "26") (name "/XTALIN") (class "Default")
      (node (ref "C2") (pin "2") (pinfunction "2_2") (pintype "passive"))
      (node (ref "R10") (pin "2") (pinfunction "2_2") (pintype "passive"))
      (node (ref "U4") (pin "8") (pinfunction "XTALIN_8") (pintype "bidirectional"))
      (node (ref "X1") (pin "2") (pinfunction "2_2") (pintype "passive"))
    )
    (net (code "27") (name "/XTALOUT") (class "Default")
      (node (ref "C3") (pin "2") (pinfunction "2_2") (pintype "passive"))
      (node (ref "R10") (pin "1") (pinfunction "1_1") (pintype "passive"))
      (node (ref "U4") (pin "9") (pinfunction "XTALOUT_9") (pintype "bidirectional"))
      (node (ref "X1") (pin "1") (pinfunction "1_1") (pintype "passive"))
    )
    (net (code "28") (name "GND_POWER") (class "Default")
      (node (ref "ADC") (pin "4") (pinfunction "4_4") (pintype "bidirectional"))
      (node (ref "BAT") (pin "2") (pinfunction "P$2_2") (pintype "bidirectional"))
      (node (ref "BAT1") (pin "-") (pinfunction "-_-") (pintype "bidirectional"))
      (node (ref "C1") (pin "-") (pinfunction "-_-") (pintype "passive"))
      (node (ref "C10") (pin "1") (pinfunction "1_1") (pintype "passive"))
      (node (ref "C11") (pin "1") (pinfunction "1_1") (pintype "passive"))
      (node (ref "C12") (pin "1") (pinfunction "1_1") (pintype "passive"))
      (node (ref "C13") (pin "1") (pinfunction "1_1") (pintype "passive"))
      (node (ref "C14") (pin "1") (pinfunction "1_1") (pintype "passive"))
      (node (ref "C15") (pin "1") (pinfunction "1_1") (pintype "passive"))
      (node (ref "C16") (pin "2") (pinfunction "2_2") (pintype "passive"))
      (node (ref "C18") (pin "1") (pinfunction "1_1") (pintype "passive"))
      (node (ref "C19") (pin "1") (pinfunction "1_1") (pintype "passive"))
      (node (ref "C2") (pin "1") (pinfunction "1_1") (pintype "passive"))
      (node (ref "C20") (pin "1") (pinfunction "1_1") (pintype "passive"))
      (node (ref "C21") (pin "1") (pinfunction "1_1") (pintype "passive"))
      (node (ref "C22") (pin "1") (pinfunction "1_1") (pintype "passive"))
      (node (ref "C23") (pin "1") (pinfunction "1_1") (pintype "passive"))
      (node (ref "C24") (pin "1") (pinfunction "1_1") (pintype "passive"))
      (node (ref "C25") (pin "1") (pinfunction "1_1") (pintype "passive"))
      (node (ref "C26") (pin "-") (pinfunction "-_-") (pintype "passive"))
      (node (ref "C27") (pin "1") (pinfunction "1_1") (pintype "passive"))
      (node (ref "C28") (pin "1") (pinfunction "1_1") (pintype "passive"))
      (node (ref "C3") (pin "1") (pinfunction "1_1") (pintype "passive"))
      (node (ref "C30") (pin "-") (pinfunction "-_-") (pintype "passive"))
      (node (ref "C31") (pin "1") (pinfunction "1_1") (pintype "passive"))
      (node (ref "C32") (pin "2") (pinfunction "2_2") (pintype "passive"))
      (node (ref "C33") (pin "2") (pinfunction "2_2") (pintype "passive"))
      (node (ref "C34") (pin "1") (pinfunction "1_1") (pintype "passive"))
      (node (ref "C36") (pin "-") (pinfunction "-_-") (pintype "passive"))
      (node (ref "C37") (pin "1") (pinfunction "1_1") (pintype "passive"))
      (node (ref "C38") (pin "1") (pinfunction "1_1") (pintype "passive"))
      (node (ref "C40") (pin "2") (pinfunction "2_2") (pintype "passive"))
      (node (ref "C41") (pin "2") (pinfunction "2_2") (pintype "passive"))
      (node (ref "C42") (pin "1") (pinfunction "1_1") (pintype "passive"))
      (node (ref "C44") (pin "1") (pinfunction "1_1") (pintype "passive"))
      (node (ref "C45") (pin "1") (pinfunction "1_1") (pintype "passive"))
      (node (ref "C46") (pin "1") (pinfunction "1_1") (pintype "passive"))
      (node (ref "C47") (pin "1") (pinfunction "1_1") (pintype "passive"))
      (node (ref "C48") (pin "1") (pinfunction "1_1") (pintype "passive"))
      (node (ref "C49") (pin "-") (pinfunction "-_-") (pintype "passive"))
      (node (ref "C5") (pin "1") (pinfunction "1_1") (pintype "passive"))
      (node (ref "C6") (pin "1") (pinfunction "1_1") (pintype "passive"))
      (node (ref "C7") (pin "-") (pinfunction "-_-") (pintype "passive"))
      (node (ref "C8") (pin "1") (pinfunction "1_1") (pintype "passive"))
      (node (ref "C9") (pin "1") (pinfunction "1_1") (pintype "passive"))
      (node (ref "D10") (pin "1") (pinfunction "1_1") (pintype "bidirectional"))
      (node (ref "D12") (pin "1") (pinfunction "1_1") (pintype "bidirectional"))
      (node (ref "D13") (pin "3") (pinfunction "3_3") (pintype "bidirectional"))
      (node (ref "D14") (pin "3") (pinfunction "3_3") (pintype "bidirectional"))
      (node (ref "D15") (pin "3") (pinfunction "3_3") (pintype "bidirectional"))
      (node (ref "D16") (pin "3") (pinfunction "3_3") (pintype "bidirectional"))
      (node (ref "D18") (pin "3") (pinfunction "3_3") (pintype "bidirectional"))
      (node (ref "D19") (pin "3") (pinfunction "3_3") (pintype "bidirectional"))
      (node (ref "D21") (pin "3") (pinfunction "3_3") (pintype "bidirectional"))
      (node (ref "D22") (pin "3") (pinfunction "3_3") (pintype "bidirectional"))
      (node (ref "D23") (pin "3") (pinfunction "3_3") (pintype "bidirectional"))
      (node (ref "D24") (pin "1") (pinfunction "1_1") (pintype "bidirectional"))
      (node (ref "D25") (pin "3") (pinfunction "3_3") (pintype "bidirectional"))
      (node (ref "D5") (pin "3") (pinfunction "3_3") (pintype "bidirectional"))
      (node (ref "D6") (pin "+") (pinfunction "+_+") (pintype "passive"))
      (node (ref "I2C") (pin "4") (pinfunction "4_4") (pintype "bidirectional"))
      (node (ref "J2") (pin "5") (pinfunction "GND_5") (pintype "bidirectional"))
      (node (ref "J2") (pin "P1") (pinfunction "GND_P1") (pintype "bidirectional"))
      (node (ref "J2") (pin "P2") (pinfunction "GND_P2") (pintype "bidirectional"))
      (node (ref "J7") (pin "7") (pinfunction "7_7") (pintype "bidirectional"))
      (node (ref "J9") (pin "6") (pinfunction "6_6") (pintype "bidirectional"))
      (node (ref "J9") (pin "7") (pinfunction "7_7") (pintype "bidirectional"))
      (node (ref "Q11") (pin "3") (pinfunction "D_3") (pintype "passive"))
      (node (ref "Q4") (pin "2") (pinfunction "S_2") (pintype "passive"))
      (node (ref "Q7") (pin "2") (pinfunction "S_2") (pintype "passive"))
      (node (ref "R17") (pin "2") (pinfunction "2_2") (pintype "passive"))
      (node (ref "R21") (pin "1") (pinfunction "1_1") (pintype "passive"))
      (node (ref "R29") (pin "1") (pinfunction "1_1") (pintype "passive"))
      (node (ref "R3") (pin "1") (pinfunction "1_1") (pintype "passive"))
      (node (ref "R33") (pin "2") (pinfunction "2_2") (pintype "passive"))
      (node (ref "R37") (pin "1") (pinfunction "1_1") (pintype "passive"))
      (node (ref "R37") (pin "2") (pinfunction "1_2") (pintype "passive"))
      (node (ref "R37") (pin "3") (pinfunction "1_3") (pintype "passive"))
      (node (ref "R37") (pin "4") (pinfunction "1_4") (pintype "passive"))
      (node (ref "R44") (pin "2") (pinfunction "2_2") (pintype "passive"))
      (node (ref "R53") (pin "2") (pinfunction "2_2") (pintype "passive"))
      (node (ref "R56") (pin "1") (pinfunction "1_1") (pintype "passive"))
      (node (ref "RST") (pin "B0") (pinfunction "B0_B0") (pintype "bidirectional"))
      (node (ref "RST") (pin "B1") (pinfunction "B1_B1") (pintype "bidirectional"))
      (node (ref "SIM") (pin "6") (pinfunction "GND_6") (pintype "bidirectional"))
      (node (ref "SIM") (pin "P1") (pinfunction "7_P1") (pintype "bidirectional"))
      (node (ref "SIM") (pin "P2") (pinfunction "8_P2") (pintype "bidirectional"))
      (node (ref "SOLAR") (pin "2") (pinfunction "P$2_2") (pintype "bidirectional"))
      (node (ref "SPI") (pin "4") (pinfunction "4_4") (pintype "bidirectional"))
      (node (ref "SWD") (pin "4") (pinfunction "P$4_4") (pintype "bidirectional"))
      (node (ref "U2") (pin "1") (pinfunction "TEMP_1") (pintype "input"))
      (node (ref "U2") (pin "3") (pinfunction "GND_3") (pintype "power_in"))
      (node (ref "U3") (pin "4") (pinfunction "GND_4") (pintype "bidirectional"))
      (node (ref "U4") (pin "54") (pinfunction "VSS_54") (pintype "bidirectional"))
      (node (ref "U4") (pin "7") (pinfunction "VSS_7") (pintype "bidirectional"))
      (node (ref "U5") (pin "2") (pinfunction "GND_2") (pintype "power_in"))
      (node (ref "U6") (pin "1") (pinfunction "A0_1") (pintype "bidirectional"))
      (node (ref "U6") (pin "2") (pinfunction "A1_2") (pintype "bidirectional"))
      (node (ref "U6") (pin "3") (pinfunction "A2_3") (pintype "bidirectional"))
      (node (ref "U6") (pin "4") (pinfunction "GND_4") (pintype "bidirectional"))
      (node (ref "U6") (pin "7") (pinfunction "WP_7") (pintype "bidirectional"))
      (node (ref "U7") (pin "11") (pinfunction "GND_11") (pintype "bidirectional"))
      (node (ref "U7") (pin "76") (pinfunction "GND_76") (pintype "bidirectional"))
      (node (ref "U7") (pin "77") (pinfunction "GND_77") (pintype "bidirectional"))
      (node (ref "U7") (pin "78") (pinfunction "GND_78") (pintype "bidirectional"))
      (node (ref "U7") (pin "79") (pinfunction "GND_79") (pintype "bidirectional"))
      (node (ref "U7") (pin "80") (pinfunction "GND_80") (pintype "bidirectional"))
      (node (ref "U7") (pin "P1") (pinfunction "GND_P1") (pintype "bidirectional"))
      (node (ref "U7") (pin "P2") (pinfunction "GND_P2") (pintype "bidirectional"))
      (node (ref "U7") (pin "P3") (pinfunction "GND_P3") (pintype "bidirectional"))
      (node (ref "U7") (pin "P4") (pinfunction "GND_P4") (pintype "bidirectional"))
      (node (ref "UART") (pin "4") (pinfunction "4_4") (pintype "bidirectional"))
    )
    (net (code "29") (name "Net-(C1-Pad+)") (class "Default")
      (node (ref "C1") (pin "+") (pinfunction "+_+") (pintype "passive"))
      (node (ref "C15") (pin "2") (pinfunction "2_2") (pintype "passive"))
      (node (ref "C17") (pin "2") (pinfunction "2_2") (pintype "passive"))
      (node (ref "L1") (pin "2") (pinfunction "2_2") (pintype "passive"))
      (node (ref "L2") (pin "1") (pinfunction "1_1") (pintype "passive"))
      (node (ref "R16") (pin "2") (pinfunction "2_2") (pintype "passive"))
    )
    (net (code "30") (name "Net-(C21-Pad2)") (class "Default")
      (node (ref "C21") (pin "2") (pinfunction "2_2") (pintype "passive"))
      (node (ref "C4") (pin "2") (pinfunction "2_2") (pintype "passive"))
      (node (ref "D20") (pin "+") (pinfunction "+_+") (pintype "passive"))
      (node (ref "R12") (pin "2") (pinfunction "2_2") (pintype "passive"))
      (node (ref "R15") (pin "1") (pinfunction "1_1") (pintype "passive"))
    )
    (net (code "31") (name "Net-(D7--)") (class "Default")
      (node (ref "C36") (pin "+") (pinfunction "+_+") (pintype "passive"))
      (node (ref "D7") (pin "1") (pinfunction "-_1") (pintype "passive"))
      (node (ref "Q3") (pin "2") (pinfunction "S_2") (pintype "passive"))
      (node (ref "Q9") (pin "2") (pinfunction "S_2") (pintype "passive"))
      (node (ref "R18") (pin "2") (pinfunction "2_2") (pintype "passive"))
      (node (ref "R19") (pin "2") (pinfunction "2_2") (pintype "passive"))
      (node (ref "R42") (pin "1") (pinfunction "1_1") (pintype "passive"))
      (node (ref "U2") (pin "4") (pinfunction "VIN_4") (pintype "input"))
    )
    (net (code "32") (name "Net-(D9-Pad+)") (class "Default")
      (node (ref "D9") (pin "+") (pinfunction "+_+") (pintype "passive"))
      (node (ref "L3") (pin "2") (pinfunction "2_2") (pintype "passive"))
    )
    (net (code "33") (name "Net-(D11-Pad-)") (class "Default")
      (node (ref "D11") (pin "-") (pinfunction "-_-") (pintype "passive"))
      (node (ref "R35") (pin "1") (pinfunction "1_1") (pintype "passive"))
    )
    (net (code "34") (name "Net-(D17--)") (class "Default")
      (node (ref "C8") (pin "2") (pinfunction "2_2") (pintype "passive"))
      (node (ref "D17") (pin "1") (pinfunction "-_1") (pintype "passive"))
      (node (ref "Q10") (pin "2") (pinfunction "S_2") (pintype "passive"))
      (node (ref "Q5") (pin "2") (pinfunction "S_2") (pintype "passive"))
      (node (ref "R27") (pin "1") (pinfunction "1_1") (pintype "passive"))
      (node (ref "R43") (pin "1") (pinfunction "1_1") (pintype "passive"))
    )
    (net (code "35") (name "Net-(D26-Pad-)") (class "Default")
      (node (ref "D26") (pin "-") (pinfunction "-_-") (pintype "passive"))
      (node (ref "R6") (pin "1") (pinfunction "1_1") (pintype "passive"))
      (node (ref "R7") (pin "1") (pinfunction "1_1") (pintype "passive"))
    )
    (net (code "36") (name "Net-(ISP-Pad+)") (class "Default")
      (node (ref "ISP") (pin "+") (pinfunction "+_+") (pintype "passive"))
      (node (ref "R24") (pin "2") (pinfunction "2_2") (pintype "passive"))
    )
    (net (code "37") (name "Net-(J2-DM)") (class "Default")
      (node (ref "D5") (pin "2") (pinfunction "2_2") (pintype "bidirectional"))
      (node (ref "J2") (pin "2") (pinfunction "DM_2") (pintype "bidirectional"))
      (node (ref "R23") (pin "1") (pinfunction "1_1") (pintype "passive"))
    )
    (net (code "38") (name "Net-(J2-DP)") (class "Default")
      (node (ref "D5") (pin "1") (pinfunction "1_1") (pintype "bidirectional"))
      (node (ref "J2") (pin "3") (pinfunction "DP_3") (pintype "bidirectional"))
      (node (ref "R1") (pin "1") (pinfunction "1_1") (pintype "passive"))
      (node (ref "R2") (pin "1") (pinfunction "1_1") (pintype "passive"))
    )
    (net (code "39") (name "Net-(J2-VCC)") (class "Default")
      (node (ref "F1") (pin "1") (pinfunction "1_1") (pintype "bidirectional"))
      (node (ref "J2") (pin "1") (pinfunction "VCC_1") (pintype "bidirectional"))
      (node (ref "TP1") (pin "T") (pinfunction "T_T") (pintype "bidirectional"))
    )
    (net (code "40") (name "Net-(L4-Pad1)") (class "Default")
      (node (ref "L4") (pin "1") (pinfunction "1_1") (pintype "passive"))
      (node (ref "MIC") (pin "1") (pinfunction "1_1") (pintype "bidirectional"))
    )
    (net (code "41") (name "Net-(L5-Pad1)") (class "Default")
      (node (ref "L5") (pin "1") (pinfunction "1_1") (pintype "passive"))
      (node (ref "MIC") (pin "2") (pinfunction "2_2") (pintype "bidirectional"))
    )
    (net (code "42") (name "Net-(L7-Pad2)") (class "Default")
      (node (ref "L7") (pin "2") (pinfunction "2_2") (pintype "passive"))
      (node (ref "SPK") (pin "2") (pinfunction "2_2") (pintype "bidirectional"))
    )
    (net (code "43") (name "Net-(L8-Pad2)") (class "Default")
      (node (ref "L8") (pin "2") (pinfunction "2_2") (pintype "passive"))
      (node (ref "SPK") (pin "1") (pinfunction "1_1") (pintype "bidirectional"))
    )
    (net (code "44") (name "Net-(M_ON-Pad+)") (class "Default")
      (node (ref "M_ON") (pin "+") (pinfunction "+_+") (pintype "passive"))
      (node (ref "R41") (pin "1") (pinfunction "1_1") (pintype "passive"))
    )
    (net (code "45") (name "Net-(Q1-G)") (class "Default")
      (node (ref "Q1") (pin "1") (pinfunction "G_1") (pintype "passive"))
      (node (ref "R30") (pin "1") (pinfunction "1_1") (pintype "passive"))
      (node (ref "R9") (pin "1") (pinfunction "1_1") (pintype "passive"))
    )
    (net (code "46") (name "Net-(Q2-D)") (class "Default")
      (node (ref "Q2") (pin "3") (pinfunction "D_3") (pintype "passive"))
      (node (ref "R1") (pin "2") (pinfunction "2_2") (pintype "passive"))
    )
    (net (code "47") (name "Net-(Q3-G)") (class "Default")
      (node (ref "Q3") (pin "1") (pinfunction "G_1") (pintype "passive"))
      (node (ref "Q4") (pin "3") (pinfunction "D_3") (pintype "passive"))
      (node (ref "R42") (pin "2") (pinfunction "2_2") (pintype "passive"))
    )
    (net (code "48") (name "Net-(Q4-G)") (class "Default")
      (node (ref "Q4") (pin "1") (pinfunction "G_1") (pintype "passive"))
      (node (ref "R8") (pin "1") (pinfunction "1_1") (pintype "passive"))
    )
    (net (code "49") (name "Net-(Q5-G)") (class "Default")
      (node (ref "Q5") (pin "1") (pinfunction "G_1") (pintype "passive"))
      (node (ref "R27") (pin "2") (pinfunction "2_2") (pintype "passive"))
      (node (ref "R57") (pin "2") (pinfunction "2_2") (pintype "passive"))
    )
    (net (code "50") (name "Net-(Q6-D)") (class "Default")
      (node (ref "Q6") (pin "3") (pinfunction "D_3") (pintype "passive"))
      (node (ref "Q7") (pin "1") (pinfunction "G_1") (pintype "passive"))
      (node (ref "R56") (pin "2") (pinfunction "2_2") (pintype "passive"))
    )
    (net (code "51") (name "Net-(Q6-G)") (class "Default")
      (node (ref "Q6") (pin "1") (pinfunction "G_1") (pintype "passive"))
      (node (ref "R22") (pin "1") (pinfunction "1_1") (pintype "passive"))
      (node (ref "R58") (pin "1") (pinfunction "1_1") (pintype "passive"))
    )
    (net (code "52") (name "Net-(Q7-D)") (class "Default")
      (node (ref "Q7") (pin "3") (pinfunction "D_3") (pintype "passive"))
      (node (ref "R57") (pin "1") (pinfunction "1_1") (pintype "passive"))
    )
    (net (code "53") (name "Net-(Q9-G)") (class "Default")
      (node (ref "Q9") (pin "1") (pinfunction "G_1") (pintype "passive"))
      (node (ref "R28") (pin "1") (pinfunction "1_1") (pintype "passive"))
    )
    (net (code "54") (name "Net-(Q10-G)") (class "Default")
      (node (ref "Q10") (pin "1") (pinfunction "G_1") (pintype "passive"))
      (node (ref "R31") (pin "1") (pinfunction "1_1") (pintype "passive"))
    )
    (net (code "55") (name "Net-(Q11-G)") (class "Default")
      (node (ref "Q11") (pin "1") (pinfunction "G_1") (pintype "passive"))
      (node (ref "R25") (pin "2") (pinfunction "2_2") (pintype "passive"))
      (node (ref "R34") (pin "2") (pinfunction "2_2") (pintype "passive"))
    )
    (net (code "56") (name "Net-(Q11-S)") (class "Default")
      (node (ref "ISP") (pin "-") (pinfunction "-_-") (pintype "passive"))
      (node (ref "Q11") (pin "2") (pinfunction "S_2") (pintype "passive"))
    )
    (net (code "57") (name "Net-(R37A-2)") (class "Default")
      (node (ref "D1") (pin "-") (pinfunction "-_-") (pintype "passive"))
      (node (ref "R37") (pin "8") (pinfunction "2_8") (pintype "passive"))
    )
    (net (code "58") (name "Net-(R37B-2)") (class "Default")
      (node (ref "D2") (pin "-") (pinfunction "-_-") (pintype "passive"))
      (node (ref "R37") (pin "7") (pinfunction "2_7") (pintype "passive"))
    )
    (net (code "59") (name "Net-(R37C-2)") (class "Default")
      (node (ref "D3") (pin "-") (pinfunction "-_-") (pintype "passive"))
      (node (ref "R37") (pin "6") (pinfunction "2_6") (pintype "passive"))
    )
    (net (code "60") (name "Net-(R37D-2)") (class "Default")
      (node (ref "D4") (pin "-") (pinfunction "-_-") (pintype "passive"))
      (node (ref "R37") (pin "5") (pinfunction "2_5") (pintype "passive"))
    )
    (net (code "61") (name "Net-(R45-Pad1)") (class "Default")
      (node (ref "R45") (pin "1") (pinfunction "1_1") (pintype "passive"))
      (node (ref "SPI") (pin "6") (pinfunction "6_6") (pintype "bidirectional"))
    )
    (net (code "62") (name "Net-(SIM-CLK)") (class "Default")
      (node (ref "C46") (pin "2") (pinfunction "2_2") (pintype "passive"))
      (node (ref "D13") (pin "2") (pinfunction "2_2") (pintype "bidirectional"))
      (node (ref "R32") (pin "1") (pinfunction "1_1") (pintype "passive"))
      (node (ref "SIM") (pin "3") (pinfunction "CLK_3") (pintype "bidirectional"))
    )
    (net (code "63") (name "Net-(SIM-I{slash}O)") (class "Default")
      (node (ref "C47") (pin "2") (pinfunction "2_2") (pintype "passive"))
      (node (ref "D14") (pin "1") (pinfunction "1_1") (pintype "bidirectional"))
      (node (ref "R48") (pin "1") (pinfunction "1_1") (pintype "passive"))
      (node (ref "SIM") (pin "4") (pinfunction "I/O_4") (pintype "bidirectional"))
    )
    (net (code "64") (name "Net-(SIM-RST)") (class "Default")
      (node (ref "C45") (pin "2") (pinfunction "2_2") (pintype "passive"))
      (node (ref "D13") (pin "1") (pinfunction "1_1") (pintype "bidirectional"))
      (node (ref "R47") (pin "1") (pinfunction "1_1") (pintype "passive"))
      (node (ref "SIM") (pin "2") (pinfunction "RST_2") (pintype "bidirectional"))
    )
    (net (code "65") (name "Net-(SIM-VCC)") (class "Default")
      (node (ref "C44") (pin "2") (pinfunction "2_2") (pintype "passive"))
      (node (ref "C48") (pin "2") (pinfunction "2_2") (pintype "passive"))
      (node (ref "D14") (pin "2") (pinfunction "2_2") (pintype "bidirectional"))
      (node (ref "SIM") (pin "1") (pinfunction "VCC_1") (pintype "bidirectional"))
      (node (ref "SIM") (pin "5") (pinfunction "VPP_5") (pintype "bidirectional"))
      (node (ref "U7") (pin "75") (pinfunction "VSIM2_75") (pintype "bidirectional"))
    )
    (net (code "66") (name "Net-(SWD-P$1)") (class "Default")
      (node (ref "D27") (pin "-") (pinfunction "-_-") (pintype "passive"))
      (node (ref "SWD") (pin "1") (pinfunction "P$1_1") (pintype "bidirectional"))
    )
    (net (code "67") (name "Net-(U2-CHRG)") (class "Default")
      (node (ref "R55") (pin "2") (pinfunction "2_2") (pintype "passive"))
      (node (ref "U2") (pin "7") (pinfunction "CHRG_7") (pintype "bidirectional"))
    )
    (net (code "68") (name "Net-(U2-DONE)") (class "Default")
      (node (ref "R54") (pin "2") (pinfunction "2_2") (pintype "passive"))
      (node (ref "U2") (pin "6") (pinfunction "DONE_6") (pintype "bidirectional"))
    )
    (net (code "69") (name "Net-(U2-ISET)") (class "Default")
      (node (ref "R3") (pin "2") (pinfunction "2_2") (pintype "passive"))
      (node (ref "U2") (pin "2") (pinfunction "ISET_2") (pintype "bidirectional"))
    )
    (net (code "70") (name "Net-(U3-VCC)") (class "Default")
      (node (ref "BAT1") (pin "+") (pinfunction "+_+") (pintype "bidirectional"))
      (node (ref "C16") (pin "1") (pinfunction "1_1") (pintype "passive"))
      (node (ref "R35") (pin "2") (pinfunction "2_2") (pintype "passive"))
      (node (ref "R49") (pin "2") (pinfunction "2_2") (pintype "passive"))
      (node (ref "R50") (pin "2") (pinfunction "2_2") (pintype "passive"))
      (node (ref "R51") (pin "2") (pinfunction "2_2") (pintype "passive"))
      (node (ref "U3") (pin "8") (pinfunction "VCC_8") (pintype "bidirectional"))
    )
    (net (code "71") (name "Net-(U3-X1)") (class "Default")
      (node (ref "C9") (pin "2") (pinfunction "2_2") (pintype "passive"))
      (node (ref "U3") (pin "1") (pinfunction "X1_1") (pintype "bidirectional"))
      (node (ref "X2") (pin "2") (pinfunction "2_2") (pintype "passive"))
    )
    (net (code "72") (name "Net-(U3-X2)") (class "Default")
      (node (ref "C14") (pin "2") (pinfunction "2_2") (pintype "passive"))
      (node (ref "U3") (pin "2") (pinfunction "X2_2") (pintype "bidirectional"))
      (node (ref "X2") (pin "1") (pinfunction "1_1") (pintype "passive"))
    )
    (net (code "73") (name "Net-(U5-SW)") (class "Default")
      (node (ref "D6") (pin "-") (pinfunction "-_-") (pintype "passive"))
      (node (ref "L1") (pin "1") (pinfunction "1_1") (pintype "passive"))
      (node (ref "U5") (pin "3") (pinfunction "SW_3") (pintype "bidirectional"))
    )
    (net (code "74") (name "Net-(U5-VFB)") (class "Default")
      (node (ref "C17") (pin "1") (pinfunction "1_1") (pintype "passive"))
      (node (ref "R16") (pin "1") (pinfunction "1_1") (pintype "passive"))
      (node (ref "R17") (pin "1") (pinfunction "1_1") (pintype "passive"))
      (node (ref "U5") (pin "5") (pinfunction "VFB_5") (pintype "input"))
    )
    (net (code "75") (name "Net-(U7-ADC3_BAT_ID)") (class "Default")
      (node (ref "R44") (pin "1") (pinfunction "1_1") (pintype "passive"))
      (node (ref "U7") (pin "8") (pinfunction "ADC3_BAT_ID_8") (pintype "bidirectional"))
    )
    (net (code "76") (name "Net-(U7-GPIO29{slash}SIM2_IO)") (class "Default")
      (node (ref "R48") (pin "2") (pinfunction "2_2") (pintype "passive"))
      (node (ref "U7") (pin "72") (pinfunction "GPIO29/SIM2_IO_72") (pintype "bidirectional"))
    )
    (net (code "77") (name "Net-(U7-GPIO30{slash}SIM2_CLK)") (class "Default")
      (node (ref "R32") (pin "2") (pinfunction "2_2") (pintype "passive"))
      (node (ref "U7") (pin "73") (pinfunction "GPIO30/SIM2_CLK_73") (pintype "bidirectional"))
    )
    (net (code "78") (name "Net-(U7-GPIO31{slash}SIM2_RST)") (class "Default")
      (node (ref "R47") (pin "2") (pinfunction "2_2") (pintype "passive"))
      (node (ref "U7") (pin "74") (pinfunction "GPIO31/SIM2_RST_74") (pintype "bidirectional"))
    )
    (net (code "79") (name "Net-(U7-GPIO70{slash}EINT4_SIM_DET)") (class "Default")
      (node (ref "R53") (pin "1") (pinfunction "1_1") (pintype "passive"))
      (node (ref "U7") (pin "9") (pinfunction "GPIO70/EINT4_SIM_DET_9") (pintype "bidirectional"))
    )
    (net (code "80") (name "Net-(U7-MIC0N)") (class "Default")
      (node (ref "C29") (pin "2") (pinfunction "2_2") (pintype "passive"))
      (node (ref "C32") (pin "1") (pinfunction "1_1") (pintype "passive"))
      (node (ref "C33") (pin "1") (pinfunction "1_1") (pintype "passive"))
      (node (ref "C35") (pin "2") (pinfunction "2_2") (pintype "passive"))
      (node (ref "D25") (pin "1") (pinfunction "1_1") (pintype "bidirectional"))
      (node (ref "L5") (pin "2") (pinfunction "2_2") (pintype "passive"))
      (node (ref "U7") (pin "37") (pinfunction "MIC0N_37") (pintype "bidirectional"))
    )
    (net (code "81") (name "Net-(U7-MIC0P)") (class "Default")
      (node (ref "C28") (pin "2") (pinfunction "2_2") (pintype "passive"))
      (node (ref "C29") (pin "1") (pinfunction "1_1") (pintype "passive"))
      (node (ref "C34") (pin "2") (pinfunction "2_2") (pintype "passive"))
      (node (ref "C35") (pin "1") (pinfunction "1_1") (pintype "passive"))
      (node (ref "D25") (pin "2") (pinfunction "2_2") (pintype "bidirectional"))
      (node (ref "L4") (pin "2") (pinfunction "2_2") (pintype "passive"))
      (node (ref "U7") (pin "38") (pinfunction "MIC0P_38") (pintype "bidirectional"))
    )
    (net (code "82") (name "Net-(U7-ON_OFF)") (class "Default")
      (node (ref "R39") (pin "1") (pinfunction "1_1") (pintype "passive"))
      (node (ref "TP9") (pin "T") (pinfunction "T_T") (pintype "bidirectional"))
      (node (ref "U7") (pin "10") (pinfunction "ON_OFF_10") (pintype "bidirectional"))
    )
    (net (code "83") (name "Net-(U7-SPK+)") (class "Default")
      (node (ref "C39") (pin "2") (pinfunction "2_2") (pintype "passive"))
      (node (ref "C40") (pin "1") (pinfunction "1_1") (pintype "passive"))
      (node (ref "C41") (pin "1") (pinfunction "1_1") (pintype "passive"))
      (node (ref "C43") (pin "2") (pinfunction "2_2") (pintype "passive"))
      (node (ref "L8") (pin "1") (pinfunction "1_1") (pintype "passive"))
      (node (ref "U7") (pin "42") (pinfunction "SPK+_42") (pintype "bidirectional"))
    )
    (net (code "84") (name "Net-(U7-SPK-)") (class "Default")
      (node (ref "C38") (pin "2") (pinfunction "2_2") (pintype "passive"))
      (node (ref "C39") (pin "1") (pinfunction "1_1") (pintype "passive"))
      (node (ref "C42") (pin "2") (pinfunction "2_2") (pintype "passive"))
      (node (ref "C43") (pin "1") (pinfunction "1_1") (pintype "passive"))
      (node (ref "L7") (pin "1") (pinfunction "1_1") (pintype "passive"))
      (node (ref "U7") (pin "41") (pinfunction "SPK-_41") (pintype "bidirectional"))
    )
    (net (code "85") (name "Net-(U7-SYSRST)") (class "Default")
      (node (ref "R40") (pin "2") (pinfunction "2_2") (pintype "passive"))
      (node (ref "U7") (pin "71") (pinfunction "SYSRST_71") (pintype "bidirectional"))
    )
    (net (code "86") (name "Net-(U7-VBAT{slash}CHGOUT)") (class "Default")
      (node (ref "R38") (pin "1") (pinfunction "1_1") (pintype "passive"))
      (node (ref "U7") (pin "5") (pinfunction "VBAT/CHGOUT_5") (pintype "bidirectional"))
    )
    (net (code "87") (name "Net-(U7-VDD_2V8)") (class "Default")
      (node (ref "R41") (pin "2") (pinfunction "2_2") (pintype "passive"))
      (node (ref "U7") (pin "49") (pinfunction "VDD_2V8_49") (pintype "bidirectional"))
    )
    (net (code "88") (name "PIO0_0{slash}RES") (class "Default")
      (node (ref "R15") (pin "2") (pinfunction "2_2") (pintype "passive"))
      (node (ref "U4") (pin "4") (pinfunction "~{RESET}/PIO0_0_4") (pintype "bidirectional"))
    )
    (net (code "89") (name "PIO0_1") (class "Default")
      (node (ref "R14") (pin "2") (pinfunction "2_2") (pintype "passive"))
      (node (ref "U4") (pin "5") (pinfunction "PIO0_1_5") (pintype "bidirectional"))
    )
    (net (code "90") (name "PIO0_3") (class "Default")
      (node (ref "R11") (pin "2") (pinfunction "2_2") (pintype "passive"))
      (node (ref "R33") (pin "1") (pinfunction "1_1") (pintype "passive"))
      (node (ref "U4") (pin "19") (pinfunction "PIO0_3_19") (pintype "bidirectional"))
    )
    (net (code "91") (name "PIO0_4") (class "Default")
      (node (ref "D21") (pin "1") (pinfunction "1_1") (pintype "bidirectional"))
      (node (ref "I2C") (pin "1") (pinfunction "1_1") (pintype "bidirectional"))
      (node (ref "J7") (pin "10") (pinfunction "10_10") (pintype "bidirectional"))
      (node (ref "R50") (pin "1") (pinfunction "1_1") (pintype "passive"))
      (node (ref "R7") (pin "2") (pinfunction "2_2") (pintype "passive"))
      (node (ref "U3") (pin "6") (pinfunction "SCL_6") (pintype "bidirectional"))
      (node (ref "U4") (pin "20") (pinfunction "PIO0_4_20") (pintype "bidirectional"))
      (node (ref "U6") (pin "6") (pinfunction "SCL_6") (pintype "bidirectional"))
    )
    (net (code "92") (name "PIO0_5") (class "Default")
      (node (ref "D21") (pin "2") (pinfunction "2_2") (pintype "bidirectional"))
      (node (ref "I2C") (pin "2") (pinfunction "2_2") (pintype "bidirectional"))
      (node (ref "J7") (pin "9") (pinfunction "9_9") (pintype "bidirectional"))
      (node (ref "R49") (pin "1") (pinfunction "1_1") (pintype "passive"))
      (node (ref "R6") (pin "2") (pinfunction "2_2") (pintype "passive"))
      (node (ref "U3") (pin "5") (pinfunction "SDA_5") (pintype "bidirectional"))
      (node (ref "U4") (pin "21") (pinfunction "PIO0_5_21") (pintype "bidirectional"))
      (node (ref "U6") (pin "5") (pinfunction "SDA_5") (pintype "bidirectional"))
    )
    (net (code "93") (name "PIO0_6") (class "Default")
      (node (ref "Q2") (pin "1") (pinfunction "G_1") (pintype "passive"))
      (node (ref "R25") (pin "1") (pinfunction "1_1") (pintype "passive"))
      (node (ref "U4") (pin "29") (pinfunction "PIO0_6_29") (pintype "bidirectional"))
    )
    (net (code "94") (name "PIO0_10") (class "Default")
      (node (ref "R4") (pin "2") (pinfunction "2_2") (pintype "passive"))
      (node (ref "SWD") (pin "3") (pinfunction "P$3_3") (pintype "bidirectional"))
      (node (ref "U4") (pin "38") (pinfunction "SWCLK/PIO0_10_38") (pintype "bidirectional"))
    )
    (net (code "95") (name "PIO0_11") (class "Default")
      (node (ref "ADC") (pin "2") (pinfunction "2_2") (pintype "bidirectional"))
      (node (ref "D18") (pin "2") (pinfunction "2_2") (pintype "bidirectional"))
      (node (ref "J10") (pin "1") (pinfunction "1_1") (pintype "bidirectional"))
      (node (ref "U4") (pin "42") (pinfunction "TDI/PIO0_11_42") (pintype "bidirectional"))
    )
    (net (code "96") (name "PIO0_12") (class "Default")
      (node (ref "ADC") (pin "1") (pinfunction "1_1") (pintype "bidirectional"))
      (node (ref "D18") (pin "1") (pinfunction "1_1") (pintype "bidirectional"))
      (node (ref "J10") (pin "2") (pinfunction "2_2") (pintype "bidirectional"))
      (node (ref "U4") (pin "44") (pinfunction "TMS/PIO0_12_44") (pintype "bidirectional"))
    )
    (net (code "97") (name "PIO0_15") (class "Default")
      (node (ref "R5") (pin "2") (pinfunction "2_2") (pintype "passive"))
      (node (ref "SWD") (pin "2") (pinfunction "P$2_2") (pintype "bidirectional"))
      (node (ref "U4") (pin "52") (pinfunction "SWDIO/PIO0_15_52") (pintype "bidirectional"))
    )
    (net (code "98") (name "PIO0_18") (class "Default")
      (node (ref "J8") (pin "1") (pinfunction "1_1") (pintype "bidirectional"))
      (node (ref "R26") (pin "2") (pinfunction "2_2") (pintype "passive"))
      (node (ref "U4") (pin "61") (pinfunction "PIO0_18_61") (pintype "bidirectional"))
    )
    (net (code "99") (name "PIO0_19") (class "Default")
      (node (ref "J8") (pin "2") (pinfunction "2_2") (pintype "bidirectional"))
      (node (ref "R36") (pin "2") (pinfunction "2_2") (pintype "passive"))
      (node (ref "U4") (pin "62") (pinfunction "PIO0_19_62") (pintype "bidirectional"))
    )
    (net (code "100") (name "PIO0_23") (class "Default")
      (node (ref "C37") (pin "2") (pinfunction "2_2") (pintype "passive"))
      (node (ref "J9") (pin "1") (pinfunction "1_1") (pintype "bidirectional"))
      (node (ref "R20") (pin "1") (pinfunction "1_1") (pintype "passive"))
      (node (ref "R21") (pin "2") (pinfunction "2_2") (pintype "passive"))
      (node (ref "U4") (pin "56") (pinfunction "PIO0_23_56") (pintype "bidirectional"))
    )
    (net (code "101") (name "PIO1_0") (class "Default")
      (node (ref "R18") (pin "1") (pinfunction "1_1") (pintype "passive"))
      (node (ref "R54") (pin "1") (pinfunction "1_1") (pintype "passive"))
      (node (ref "U4") (pin "1") (pinfunction "PIO1_0_1") (pintype "bidirectional"))
    )
    (net (code "102") (name "PIO1_1") (class "Default")
      (node (ref "R19") (pin "1") (pinfunction "1_1") (pintype "passive"))
      (node (ref "R55") (pin "1") (pinfunction "1_1") (pintype "passive"))
      (node (ref "U4") (pin "17") (pinfunction "PIO1_1_17") (pintype "bidirectional"))
    )
    (net (code "103") (name "PIO1_2") (class "Default")
      (node (ref "R22") (pin "2") (pinfunction "2_2") (pintype "passive"))
      (node (ref "U4") (pin "34") (pinfunction "PIO1_2_34") (pintype "bidirectional"))
    )
    (net (code "104") (name "PIO1_3") (class "Default")
      (node (ref "R30") (pin "2") (pinfunction "2_2") (pintype "passive"))
      (node (ref "U4") (pin "50") (pinfunction "PIO1_3_50") (pintype "bidirectional"))
    )
    (net (code "105") (name "PIO1_6") (class "Default")
      (node (ref "R40") (pin "1") (pinfunction "1_1") (pintype "passive"))
      (node (ref "R46") (pin "1") (pinfunction "1_1") (pintype "passive"))
      (node (ref "TP8") (pin "T") (pinfunction "T_T") (pintype "bidirectional"))
      (node (ref "U4") (pin "64") (pinfunction "PIO1_6_64") (pintype "bidirectional"))
    )
    (net (code "106") (name "PIO1_7") (class "Default")
      (node (ref "D16") (pin "2") (pinfunction "2_2") (pintype "bidirectional"))
      (node (ref "R39") (pin "2") (pinfunction "2_2") (pintype "passive"))
      (node (ref "R52") (pin "2") (pinfunction "2_2") (pintype "passive"))
      (node (ref "U4") (pin "6") (pinfunction "PIO1_7_6") (pintype "bidirectional"))
    )
    (net (code "107") (name "PIO1_8") (class "Default")
      (node (ref "D1") (pin "+") (pinfunction "+_+") (pintype "passive"))
      (node (ref "U4") (pin "39") (pinfunction "PIO1_8_39") (pintype "bidirectional"))
    )
    (net (code "108") (name "PIO1_9") (class "Default")
      (node (ref "D2") (pin "+") (pinfunction "+_+") (pintype "passive"))
      (node (ref "U4") (pin "55") (pinfunction "PIO1_9_55") (pintype "bidirectional"))
    )
    (net (code "109") (name "PIO1_10") (class "Default")
      (node (ref "D3") (pin "+") (pinfunction "+_+") (pintype "passive"))
      (node (ref "U4") (pin "12") (pinfunction "PIO1_10_12") (pintype "bidirectional"))
    )
    (net (code "110") (name "PIO1_11") (class "Default")
      (node (ref "D4") (pin "+") (pinfunction "+_+") (pintype "passive"))
      (node (ref "U4") (pin "43") (pinfunction "PIO1_11_43") (pintype "bidirectional"))
    )
    (net (code "111") (name "PIO1_12") (class "Default")
      (node (ref "R51") (pin "1") (pinfunction "1_1") (pintype "passive"))
      (node (ref "U3") (pin "7") (pinfunction "SQW/~{INTB}_7") (pintype "bidirectional"))
      (node (ref "U4") (pin "59") (pinfunction "PIO1_12_59") (pintype "bidirectional"))
    )
    (net (code "112") (name "PIO1_13") (class "Default")
      (node (ref "D19") (pin "2") (pinfunction "2_2") (pintype "bidirectional"))
      (node (ref "U4") (pin "47") (pinfunction "PIO1_13_47") (pintype "bidirectional"))
      (node (ref "UART") (pin "2") (pinfunction "2_2") (pintype "bidirectional"))
    )
    (net (code "113") (name "PIO1_14") (class "Default")
      (node (ref "D19") (pin "1") (pinfunction "1_1") (pintype "bidirectional"))
      (node (ref "U4") (pin "49") (pinfunction "PIO1_14_49") (pintype "bidirectional"))
      (node (ref "UART") (pin "1") (pinfunction "1_1") (pintype "bidirectional"))
    )
    (net (code "114") (name "PIO1_15") (class "Default")
      (node (ref "M_ON") (pin "-") (pinfunction "-_-") (pintype "passive"))
      (node (ref "U4") (pin "57") (pinfunction "PIO1_15_57") (pintype "bidirectional"))
    )
    (net (code "115") (name "PIO1_20") (class "Default")
      (node (ref "D22") (pin "2") (pinfunction "2_2") (pintype "bidirectional"))
      (node (ref "SPI") (pin "2") (pinfunction "2_2") (pintype "bidirectional"))
      (node (ref "U4") (pin "18") (pinfunction "PIO1_20_18") (pintype "bidirectional"))
    )
    (net (code "116") (name "PIO1_21") (class "Default")
      (node (ref "D22") (pin "1") (pinfunction "1_1") (pintype "bidirectional"))
      (node (ref "SPI") (pin "1") (pinfunction "1_1") (pintype "bidirectional"))
      (node (ref "U4") (pin "35") (pinfunction "PIO1_21_35") (pintype "bidirectional"))
    )
    (net (code "117") (name "PIO1_22") (class "Default")
      (node (ref "D23") (pin "2") (pinfunction "2_2") (pintype "bidirectional"))
      (node (ref "SPI") (pin "5") (pinfunction "5_5") (pintype "bidirectional"))
      (node (ref "U4") (pin "51") (pinfunction "PIO1_22_51") (pintype "bidirectional"))
    )
    (net (code "118") (name "PIO1_23") (class "Default")
      (node (ref "D23") (pin "1") (pinfunction "1_1") (pintype "bidirectional"))
      (node (ref "SPI") (pin "3") (pinfunction "3_3") (pintype "bidirectional"))
      (node (ref "U4") (pin "24") (pinfunction "PIO1_23_24") (pintype "bidirectional"))
    )
    (net (code "119") (name "RESET") (class "Default")
      (node (ref "C4") (pin "1") (pinfunction "1_1") (pintype "passive"))
      (node (ref "J9") (pin "3") (pinfunction "3_3") (pintype "bidirectional"))
      (node (ref "R13") (pin "2") (pinfunction "2_2") (pintype "passive"))
      (node (ref "R14") (pin "1") (pinfunction "1_1") (pintype "passive"))
      (node (ref "RST") (pin "A0") (pinfunction "A0_A0") (pintype "bidirectional"))
      (node (ref "RST") (pin "A1") (pinfunction "A1_A1") (pintype "bidirectional"))
    )
    (net (code "120") (name "USB_5V") (class "Default")
      (node (ref "C5") (pin "2") (pinfunction "2_2") (pintype "passive"))
      (node (ref "D12") (pin "2") (pinfunction "2_2") (pintype "bidirectional"))
      (node (ref "D28") (pin "+") (pinfunction "+_+") (pintype "passive"))
      (node (ref "D7") (pin "2") (pinfunction "+_2") (pintype "passive"))
      (node (ref "F1") (pin "2") (pinfunction "2_2") (pintype "bidirectional"))
      (node (ref "R11") (pin "1") (pinfunction "1_1") (pintype "passive"))
      (node (ref "R28") (pin "2") (pinfunction "2_2") (pintype "passive"))
      (node (ref "R29") (pin "2") (pinfunction "2_2") (pintype "passive"))
      (node (ref "R31") (pin "2") (pinfunction "2_2") (pintype "passive"))
      (node (ref "R8") (pin "2") (pinfunction "2_2") (pintype "passive"))
      (node (ref "TP2") (pin "T") (pinfunction "T_T") (pintype "bidirectional"))
    )
    (net (code "121") (name "USB_DM") (class "Default")
      (node (ref "R23") (pin "2") (pinfunction "2_2") (pintype "passive"))
      (node (ref "U4") (pin "25") (pinfunction "USB_DM_25") (pintype "bidirectional"))
    )
    (net (code "122") (name "USB_DP") (class "Default")
      (node (ref "R2") (pin "2") (pinfunction "2_2") (pintype "passive"))
      (node (ref "U4") (pin "26") (pinfunction "USB_DP_26") (pintype "bidirectional"))
    )
    (net (code "123") (name "USB_ID") (class "Default")
      (node (ref "J2") (pin "4") (pinfunction "ID_4") (pintype "bidirectional"))
    )
    (net (code "124") (name "VCC_3V3") (class "Default")
      (node (ref "C10") (pin "2") (pinfunction "2_2") (pintype "passive"))
      (node (ref "C11") (pin "2") (pinfunction "2_2") (pintype "passive"))
      (node (ref "C12") (pin "2") (pinfunction "2_2") (pintype "passive"))
      (node (ref "C13") (pin "2") (pinfunction "2_2") (pintype "passive"))
      (node (ref "C23") (pin "2") (pinfunction "2_2") (pintype "passive"))
      (node (ref "C24") (pin "2") (pinfunction "2_2") (pintype "passive"))
      (node (ref "D10") (pin "2") (pinfunction "2_2") (pintype "bidirectional"))
      (node (ref "D11") (pin "+") (pinfunction "+_+") (pintype "passive"))
      (node (ref "D20") (pin "-") (pinfunction "-_-") (pintype "passive"))
      (node (ref "D27") (pin "+") (pinfunction "+_+") (pintype "passive"))
      (node (ref "J9") (pin "2") (pinfunction "2_2") (pintype "bidirectional"))
      (node (ref "J9") (pin "4") (pinfunction "4_4") (pintype "bidirectional"))
      (node (ref "L2") (pin "2") (pinfunction "2_2") (pintype "passive"))
      (node (ref "Q1") (pin "2") (pinfunction "S_2") (pintype "passive"))
      (node (ref "Q2") (pin "2") (pinfunction "S_2") (pintype "passive"))
      (node (ref "Q6") (pin "2") (pinfunction "S_2") (pintype "passive"))
      (node (ref "R12") (pin "1") (pinfunction "1_1") (pintype "passive"))
      (node (ref "R13") (pin "1") (pinfunction "1_1") (pintype "passive"))
      (node (ref "R24") (pin "1") (pinfunction "1_1") (pintype "passive"))
      (node (ref "R34") (pin "1") (pinfunction "1_1") (pintype "passive"))
      (node (ref "R4") (pin "1") (pinfunction "1_1") (pintype "passive"))
      (node (ref "R45") (pin "2") (pinfunction "2_2") (pintype "passive"))
      (node (ref "R46") (pin "2") (pinfunction "2_2") (pintype "passive"))
      (node (ref "R5") (pin "1") (pinfunction "1_1") (pintype "passive"))
      (node (ref "R58") (pin "2") (pinfunction "2_2") (pintype "passive"))
      (node (ref "R9") (pin "2") (pinfunction "2_2") (pintype "passive"))
      (node (ref "TP4") (pin "T") (pinfunction "T_T") (pintype "bidirectional"))
      (node (ref "U4") (pin "10") (pinfunction "VDD_10") (pintype "bidirectional"))
      (node (ref "U4") (pin "33") (pinfunction "VDD_33") (pintype "bidirectional"))
      (node (ref "U4") (pin "48") (pinfunction "VDD_48") (pintype "bidirectional"))
      (node (ref "U4") (pin "58") (pinfunction "VDD_58") (pintype "bidirectional"))
    )
    (net (code "125") (name "VCC_5V") (class "Default")
      (node (ref "D28") (pin "-") (pinfunction "-_-") (pintype "passive"))
      (node (ref "J9") (pin "5") (pinfunction "5_5") (pintype "bidirectional"))
    )
    (net (code "126") (name "VCC_BAT") (class "Default")
      (node (ref "BAT") (pin "1") (pinfunction "P$1_1") (pintype "bidirectional"))
      (node (ref "C26") (pin "+") (pinfunction "+_+") (pintype "passive"))
      (node (ref "L3") (pin "1") (pinfunction "1_1") (pintype "passive"))
      (node (ref "Q10") (pin "3") (pinfunction "D_3") (pintype "passive"))
      (node (ref "R20") (pin "2") (pinfunction "2_2") (pintype "passive"))
      (node (ref "U2") (pin "5") (pinfunction "BAT_5") (pintype "bidirectional"))
      (node (ref "U2") (pin "8") (pinfunction "FB_8") (pintype "input"))
    )
    (net (code "127") (name "VCC_BUCK") (class "Default")
      (node (ref "C27") (pin "2") (pinfunction "2_2") (pintype "passive"))
      (node (ref "C7") (pin "+") (pinfunction "+_+") (pintype "passive"))
      (node (ref "D17") (pin "2") (pinfunction "+_2") (pintype "passive"))
      (node (ref "D9") (pin "-") (pinfunction "-_-") (pintype "passive"))
      (node (ref "Q3") (pin "3") (pinfunction "D_3") (pintype "passive"))
      (node (ref "R43") (pin "2") (pinfunction "2_2") (pintype "passive"))
      (node (ref "TP3") (pin "T") (pinfunction "T_T") (pintype "bidirectional"))
      (node (ref "U5") (pin "1") (pinfunction "RUN_1") (pintype "bidirectional"))
      (node (ref "U5") (pin "4") (pinfunction "VIN_4") (pintype "input"))
    )
    (net (code "128") (name "VCC_EG10") (class "Default")
      (node (ref "C22") (pin "2") (pinfunction "2_2") (pintype "passive"))
      (node (ref "C30") (pin "+") (pinfunction "+_+") (pintype "passive"))
      (node (ref "C31") (pin "2") (pinfunction "2_2") (pintype "passive"))
      (node (ref "C49") (pin "+") (pinfunction "+_+") (pintype "passive"))
      (node (ref "D16") (pin "1") (pinfunction "1_1") (pintype "bidirectional"))
      (node (ref "Q5") (pin "3") (pinfunction "D_3") (pintype "passive"))
      (node (ref "R38") (pin "2") (pinfunction "2_2") (pintype "passive"))
      (node (ref "R52") (pin "1") (pinfunction "1_1") (pintype "passive"))
      (node (ref "TP7") (pin "T") (pinfunction "T_T") (pintype "bidirectional"))
      (node (ref "U7") (pin "1") (pinfunction "VBAT_1") (pintype "bidirectional"))
      (node (ref "U7") (pin "2") (pinfunction "VBAT_2") (pintype "bidirectional"))
      (node (ref "U7") (pin "3") (pinfunction "VBAT_3") (pintype "bidirectional"))
      (node (ref "U7") (pin "4") (pinfunction "VBAT_4") (pintype "bidirectional"))
    )
    (net (code "129") (name "VCC_G") (class "Default")
      (node (ref "ADC") (pin "3") (pinfunction "3_3") (pintype "bidirectional"))
      (node (ref "C18") (pin "2") (pinfunction "2_2") (pintype "passive"))
      (node (ref "C19") (pin "2") (pinfunction "2_2") (pintype "passive"))
      (node (ref "C20") (pin "2") (pinfunction "2_2") (pintype "passive"))
      (node (ref "C25") (pin "2") (pinfunction "2_2") (pintype "passive"))
      (node (ref "D26") (pin "+") (pinfunction "+_+") (pintype "passive"))
      (node (ref "I2C") (pin "3") (pinfunction "3_3") (pintype "bidirectional"))
      (node (ref "Q1") (pin "3") (pinfunction "D_3") (pintype "passive"))
      (node (ref "TP6") (pin "T") (pinfunction "T_T") (pintype "bidirectional"))
      (node (ref "U6") (pin "8") (pinfunction "VCC_8") (pintype "bidirectional"))
      (node (ref "UART") (pin "3") (pinfunction "3_3") (pintype "bidirectional"))
    )
    (net (code "130") (name "VCC_SOLAR") (class "Default")
      (node (ref "C6") (pin "2") (pinfunction "2_2") (pintype "passive"))
      (node (ref "D24") (pin "2") (pinfunction "2_2") (pintype "bidirectional"))
      (node (ref "Q9") (pin "3") (pinfunction "D_3") (pintype "passive"))
      (node (ref "SOLAR") (pin "1") (pinfunction "P$1_1") (pintype "bidirectional"))
    )
    (net (code "131") (name "unconnected-(J9-Pad8)") (class "Default")
      (node (ref "J9") (pin "8") (pinfunction "8_8") (pintype "bidirectional"))
    )
    (net (code "132") (name "unconnected-(U2-H-PadHEAT)") (class "Default")
      (node (ref "U2") (pin "HEAT") (pinfunction "H_HEAT") (pintype "bidirectional"))
    )
    (net (code "133") (name "unconnected-(U3-~{INTA}-Pad3)") (class "Default")
      (node (ref "U3") (pin "3") (pinfunction "~{INTA}_3") (pintype "bidirectional"))
    )
    (net (code "134") (name "unconnected-(U7-ADC4-Pad36)") (class "Default")
      (node (ref "U7") (pin "36") (pinfunction "ADC4_36") (pintype "bidirectional"))
    )
    (net (code "135") (name "unconnected-(U7-CHGIN{slash}USBIN-Pad6)") (class "Default")
      (node (ref "U7") (pin "6") (pinfunction "CHGIN/USBIN_6") (pintype "bidirectional"))
    )
    (net (code "136") (name "unconnected-(U7-CHGIN{slash}USBIN-Pad7)") (class "Default")
      (node (ref "U7") (pin "7") (pinfunction "CHGIN/USBIN_7") (pintype "bidirectional"))
    )
    (net (code "137") (name "unconnected-(U7-GPIO0{slash}PWM_BUZZER_EN-Pad45)") (class "Default")
      (node (ref "U7") (pin "45") (pinfunction "GPIO0/PWM_BUZZER_EN_45") (pintype "bidirectional"))
    )
    (net (code "138") (name "unconnected-(U7-GPIO1{slash}KCOL6-Pad28)") (class "Default")
      (node (ref "U7") (pin "28") (pinfunction "GPIO1/KCOL6_28") (pintype "bidirectional"))
    )
    (net (code "139") (name "unconnected-(U7-GPIO3{slash}IIC_SCK{slash}KCOL4-Pad19)") (class "Default")
      (node (ref "U7") (pin "19") (pinfunction "GPIO3/IIC_SCK/KCOL4_19") (pintype "bidirectional"))
    )
    (net (code "140") (name "unconnected-(U7-GPIO4{slash}UART1_CTS{slash}KCOL3-Pad15)") (class "Default")
      (node (ref "U7") (pin "15") (pinfunction "GPIO4/UART1_CTS/KCOL3_15") (pintype "bidirectional"))
    )
    (net (code "141") (name "unconnected-(U7-GPIO5{slash}KCOL2-Pad26)") (class "Default")
      (node (ref "U7") (pin "26") (pinfunction "GPIO5/KCOL2_26") (pintype "bidirectional"))
    )
    (net (code "142") (name "unconnected-(U7-GPIO6{slash}KCOL1-Pad29)") (class "Default")
      (node (ref "U7") (pin "29") (pinfunction "GPIO6/KCOL1_29") (pintype "bidirectional"))
    )
    (net (code "143") (name "unconnected-(U7-GPIO8{slash}INT5{slash}KROW5-Pad53)") (class "Default")
      (node (ref "U7") (pin "53") (pinfunction "GPIO8/INT5/KROW5_53") (pintype "bidirectional"))
    )
    (net (code "144") (name "unconnected-(U7-GPIO10{slash}UART1_RTS{slash}KROW3-Pad12)") (class "Default")
      (node (ref "U7") (pin "12") (pinfunction "GPIO10/UART1_RTS/KROW3_12") (pintype "bidirectional"))
    )
    (net (code "145") (name "unconnected-(U7-GPIO11{slash}KROW2-Pad55)") (class "Default")
      (node (ref "U7") (pin "55") (pinfunction "GPIO11/KROW2_55") (pintype "bidirectional"))
    )
    (net (code "146") (name "unconnected-(U7-GPIO12{slash}KROW1-Pad56)") (class "Default")
      (node (ref "U7") (pin "56") (pinfunction "GPIO12/KROW1_56") (pintype "bidirectional"))
    )
    (net (code "147") (name "unconnected-(U7-GPIO13{slash}SPI_LSDI{slash}KROW0-Pad60)") (class "Default")
      (node (ref "U7") (pin "60") (pinfunction "GPIO13/SPI_LSDI/KROW0_60") (pintype "bidirectional"))
    )
    (net (code "148") (name "unconnected-(U7-GPIO15{slash}PCM_CLK-Pad35)") (class "Default")
      (node (ref "U7") (pin "35") (pinfunction "GPIO15/PCM_CLK_35") (pintype "bidirectional"))
    )
    (net (code "149") (name "unconnected-(U7-GPIO16{slash}PCM_OUT-Pad46)") (class "Default")
      (node (ref "U7") (pin "46") (pinfunction "GPIO16/PCM_OUT_46") (pintype "bidirectional"))
    )
    (net (code "150") (name "unconnected-(U7-GPIO17{slash}PCM_IN-Pad47)") (class "Default")
      (node (ref "U7") (pin "47") (pinfunction "GPIO17/PCM_IN_47") (pintype "bidirectional"))
    )
    (net (code "151") (name "unconnected-(U7-GPIO19{slash}KROW4-Pad54)") (class "Default")
      (node (ref "U7") (pin "54") (pinfunction "GPIO19/KROW4_54") (pintype "bidirectional"))
    )
    (net (code "152") (name "unconnected-(U7-GPIO19{slash}PCM_SYNC-Pad34)") (class "Default")
      (node (ref "U7") (pin "34") (pinfunction "GPIO19/PCM_SYNC_34") (pintype "bidirectional"))
    )
    (net (code "153") (name "unconnected-(U7-GPIO20{slash}UART2_CTS{slash}UART3_RXD-Pad64)") (class "Default")
      (node (ref "U7") (pin "64") (pinfunction "GPIO20/UART2_CTS/UART3_RXD_64") (pintype "bidirectional"))
    )
    (net (code "154") (name "unconnected-(U7-GPIO21{slash}UART2_RTS{slash}UART3_TXD-Pad17)") (class "Default")
      (node (ref "U7") (pin "17") (pinfunction "GPIO21/UART2_RTS/UART3_TXD_17") (pintype "bidirectional"))
    )
    (net (code "155") (name "unconnected-(U7-GPIO22{slash}UART1_CTS{slash}UART2_RXD-Pad65)") (class "Default")
      (node (ref "U7") (pin "65") (pinfunction "GPIO22/UART1_CTS/UART2_RXD_65") (pintype "bidirectional"))
    )
    (net (code "156") (name "unconnected-(U7-GPIO23{slash}UART1_RTS{slash}UART2_TXD-Pad16)") (class "Default")
      (node (ref "U7") (pin "16") (pinfunction "GPIO23/UART1_RTS/UART2_TXD_16") (pintype "bidirectional"))
    )
    (net (code "157") (name "unconnected-(U7-GPIO26{slash}EINT0{slash}CLK04-Pad57)") (class "Default")
      (node (ref "U7") (pin "57") (pinfunction "GPIO26/EINT0/CLK04_57") (pintype "bidirectional"))
    )
    (net (code "158") (name "unconnected-(U7-GPIO27{slash}EINT1{slash}CLK03-Pad24)") (class "Default")
      (node (ref "U7") (pin "24") (pinfunction "GPIO27/EINT1/CLK03_24") (pintype "bidirectional"))
    )
    (net (code "159") (name "unconnected-(U7-GPIO27{slash}KCOL5-Pad27)") (class "Default")
      (node (ref "U7") (pin "27") (pinfunction "GPIO27/KCOL5_27") (pintype "bidirectional"))
    )
    (net (code "160") (name "unconnected-(U7-GPIO33{slash}SPI_CS{slash}CLK0_32K-Pad59)") (class "Default")
      (node (ref "U7") (pin "59") (pinfunction "GPIO33/SPI_CS/CLK0_32K_59") (pintype "bidirectional"))
    )
    (net (code "161") (name "unconnected-(U7-GPIO37{slash}UART1_DCD{slash}MCCK-Pad68)") (class "Default")
      (node (ref "U7") (pin "68") (pinfunction "GPIO37/UART1_DCD/MCCK_68") (pintype "bidirectional"))
    )
    (net (code "162") (name "unconnected-(U7-GPIO38{slash}UART1_DSR{slash}MCDA0-Pad67)") (class "Default")
      (node (ref "U7") (pin "67") (pinfunction "GPIO38/UART1_DSR/MCDA0_67") (pintype "bidirectional"))
    )
    (net (code "163") (name "unconnected-(U7-GPIO39{slash}UART1_R1{slash}MCCM0-Pad69)") (class "Default")
      (node (ref "U7") (pin "69") (pinfunction "GPIO39/UART1_R1/MCCM0_69") (pintype "bidirectional"))
    )
    (net (code "164") (name "unconnected-(U7-GPIO41{slash}USBIN_DET_INT2-Pad48)") (class "Default")
      (node (ref "U7") (pin "48") (pinfunction "GPIO41/USBIN_DET_INT2_48") (pintype "bidirectional"))
    )
    (net (code "165") (name "unconnected-(U7-GPIO43{slash}KCOL7-Pad25)") (class "Default")
      (node (ref "U7") (pin "25") (pinfunction "GPIO43/KCOL7_25") (pintype "bidirectional"))
    )
    (net (code "166") (name "unconnected-(U7-GPIO44{slash}KROW6-Pad52)") (class "Default")
      (node (ref "U7") (pin "52") (pinfunction "GPIO44/KROW6_52") (pintype "bidirectional"))
    )
    (net (code "167") (name "unconnected-(U7-GPIO45{slash}IIC_SDA{slash}KROW7-Pad62)") (class "Default")
      (node (ref "U7") (pin "62") (pinfunction "GPIO45/IIC_SDA/KROW7_62") (pintype "bidirectional"))
    )
    (net (code "168") (name "unconnected-(U7-GPIO47-Pad31)") (class "Default")
      (node (ref "U7") (pin "31") (pinfunction "GPIO47_31") (pintype "bidirectional"))
    )
    (net (code "169") (name "unconnected-(U7-GPIO48{slash}SPI_LSDA-Pad22)") (class "Default")
      (node (ref "U7") (pin "22") (pinfunction "GPIO48/SPI_LSDA_22") (pintype "bidirectional"))
    )
    (net (code "170") (name "unconnected-(U7-GPIO50-Pad63)") (class "Default")
      (node (ref "U7") (pin "63") (pinfunction "GPIO50_63") (pintype "bidirectional"))
    )
    (net (code "171") (name "unconnected-(U7-GPIO52-Pad61)") (class "Default")
      (node (ref "U7") (pin "61") (pinfunction "GPIO52_61") (pintype "bidirectional"))
    )
    (net (code "172") (name "unconnected-(U7-GPIO54-Pad23)") (class "Default")
      (node (ref "U7") (pin "23") (pinfunction "GPIO54_23") (pintype "bidirectional"))
    )
    (net (code "173") (name "unconnected-(U7-GPIO55-Pad30)") (class "Default")
      (node (ref "U7") (pin "30") (pinfunction "GPIO55_30") (pintype "bidirectional"))
    )
    (net (code "174") (name "unconnected-(U7-GPIO56-Pad58)") (class "Default")
      (node (ref "U7") (pin "58") (pinfunction "GPIO56_58") (pintype "bidirectional"))
    )
    (net (code "175") (name "unconnected-(U7-GPIO57{slash}SPI_CLK-Pad21)") (class "Default")
      (node (ref "U7") (pin "21") (pinfunction "GPIO57/SPI_CLK_21") (pintype "bidirectional"))
    )
    (net (code "176") (name "unconnected-(U7-GPIO59-Pad20)") (class "Default")
      (node (ref "U7") (pin "20") (pinfunction "GPIO59_20") (pintype "bidirectional"))
    )
    (net (code "177") (name "unconnected-(U7-GPIO60-Pad18)") (class "Default")
      (node (ref "U7") (pin "18") (pinfunction "GPIO60_18") (pintype "bidirectional"))
    )
    (net (code "178") (name "unconnected-(U7-GPIO61{slash}UART1_DTR-Pad66)") (class "Default")
      (node (ref "U7") (pin "66") (pinfunction "GPIO61/UART1_DTR_66") (pintype "bidirectional"))
    )
    (net (code "179") (name "unconnected-(U7-IO62_EXT_RST-Pad70)") (class "Default")
      (node (ref "U7") (pin "70") (pinfunction "IO62_EXT_RST_70") (pintype "bidirectional"))
    )
    (net (code "180") (name "unconnected-(U7-LED--Pad51)") (class "Default")
      (node (ref "U7") (pin "51") (pinfunction "LED-_51") (pintype "bidirectional"))
    )
    (net (code "181") (name "unconnected-(U7-MIC1N-Pad39)") (class "Default")
      (node (ref "U7") (pin "39") (pinfunction "MIC1N_39") (pintype "bidirectional"))
    )
    (net (code "182") (name "unconnected-(U7-MIC1P-Pad40)") (class "Default")
      (node (ref "U7") (pin "40") (pinfunction "MIC1P_40") (pintype "bidirectional"))
    )
    (net (code "183") (name "unconnected-(U7-REC+-Pad44)") (class "Default")
      (node (ref "U7") (pin "44") (pinfunction "REC+_44") (pintype "bidirectional"))
    )
    (net (code "184") (name "unconnected-(U7-REC--Pad43)") (class "Default")
      (node (ref "U7") (pin "43") (pinfunction "REC-_43") (pintype "bidirectional"))
    )
    (net (code "185") (name "unconnected-(U7-USB_DM-Pad32)") (class "Default")
      (node (ref "U7") (pin "32") (pinfunction "USB_DM_32") (pintype "bidirectional"))
    )
    (net (code "186") (name "unconnected-(U7-USB_DP-Pad33)") (class "Default")
      (node (ref "U7") (pin "33") (pinfunction "USB_DP_33") (pintype "bidirectional"))
    )
    (net (code "187") (name "unconnected-(U7-VRCT_IN-Pad50)") (class "Default")
      (node (ref "U7") (pin "50") (pinfunction "VRCT_IN_50") (pintype "bidirectional"))
    )
  )
)
